# CI_iCESDuck-ShieldControler.net
KiCad netlist of a schematic drawn in EasyEDA
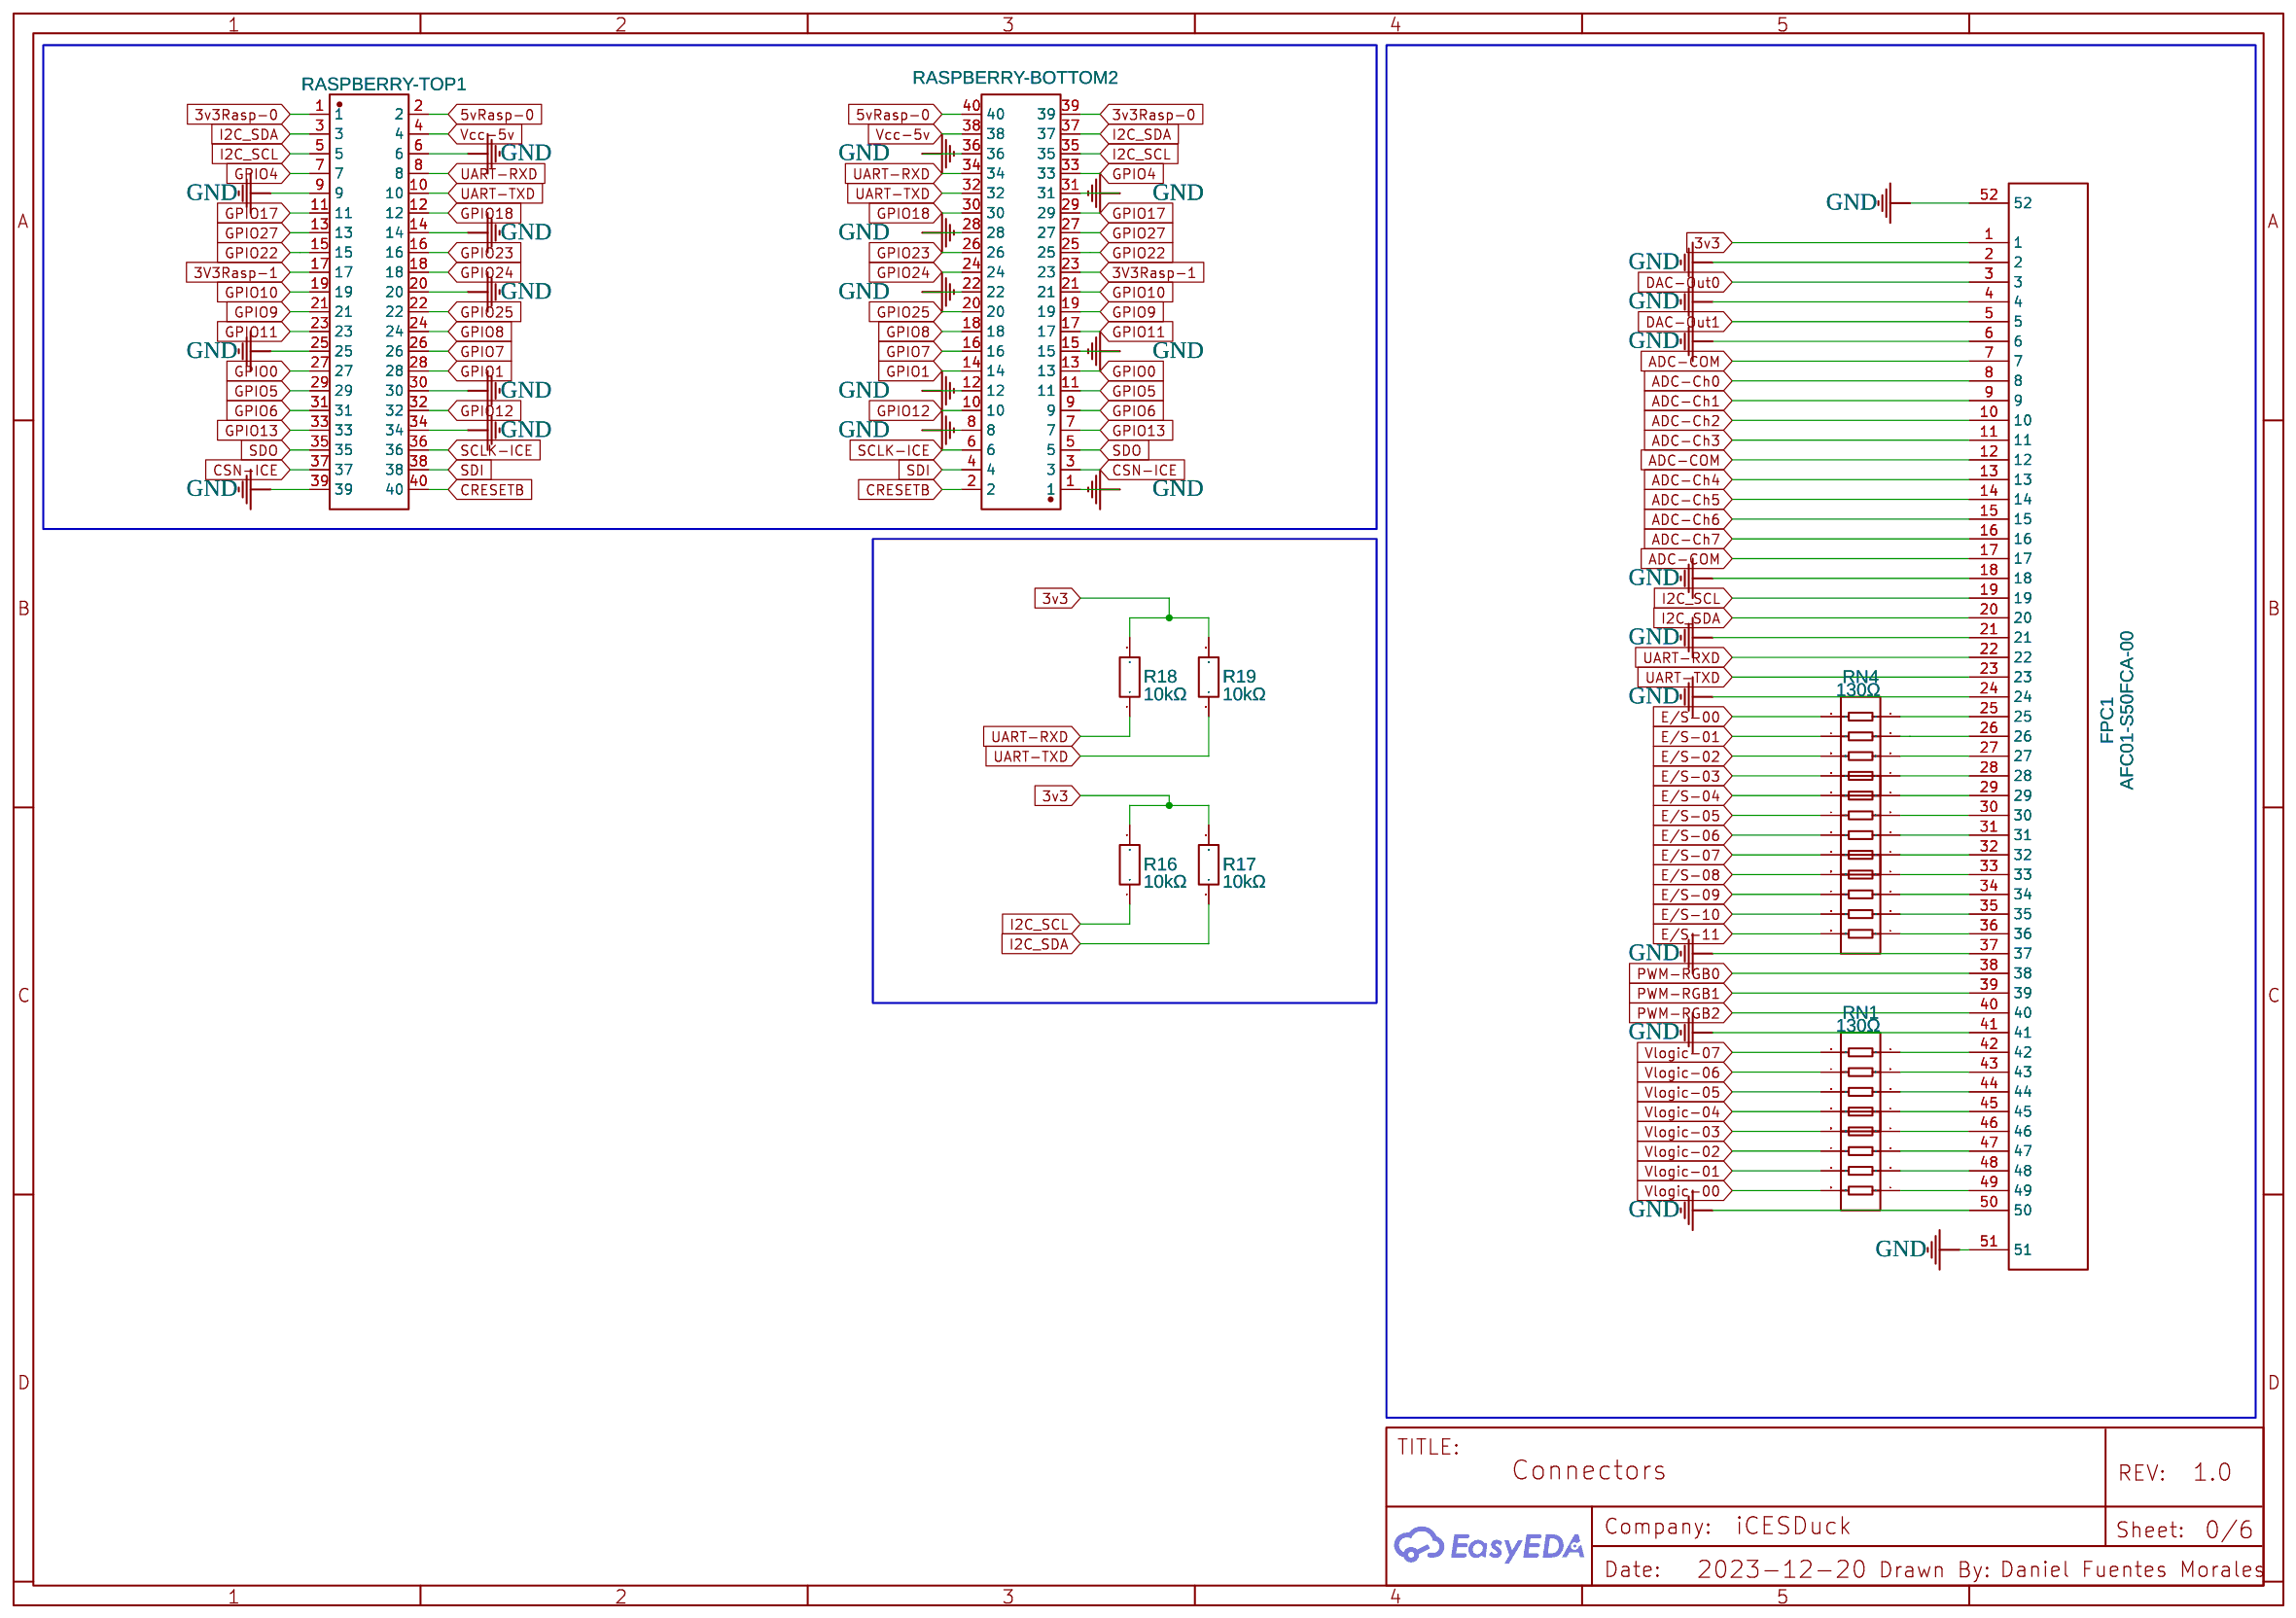
[diagram p0: Connectors]
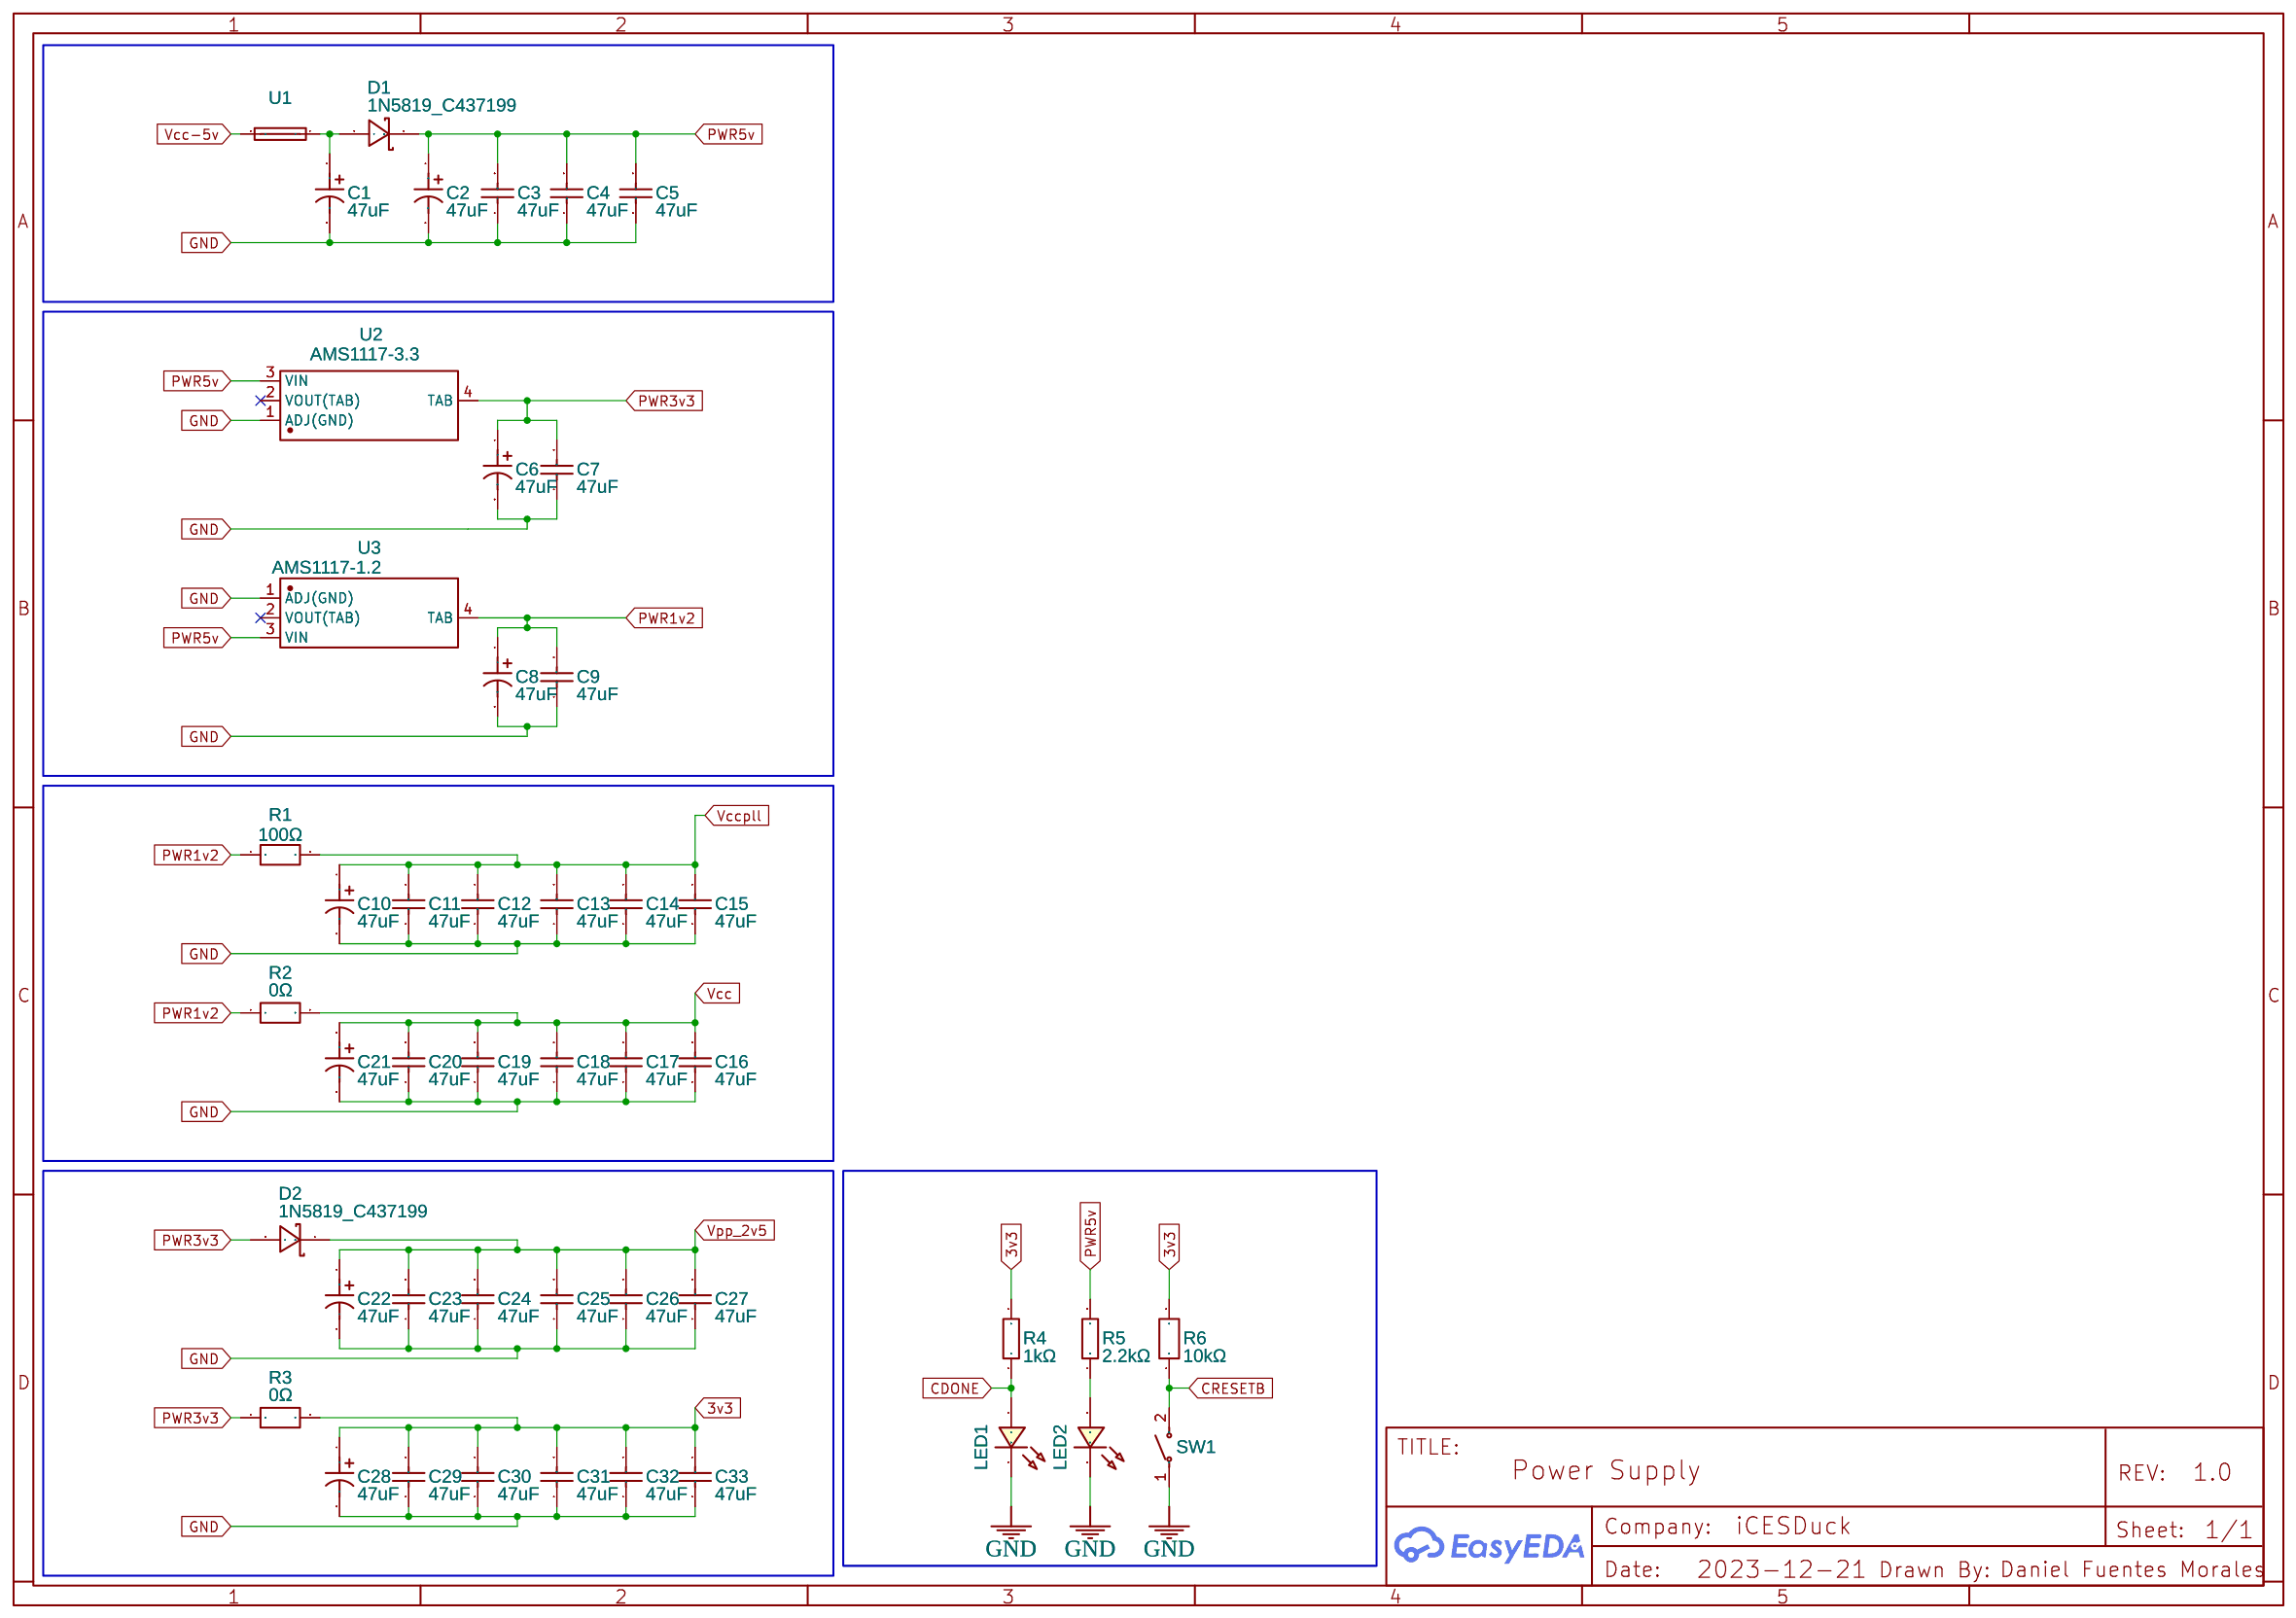
[diagram p1: power supply]
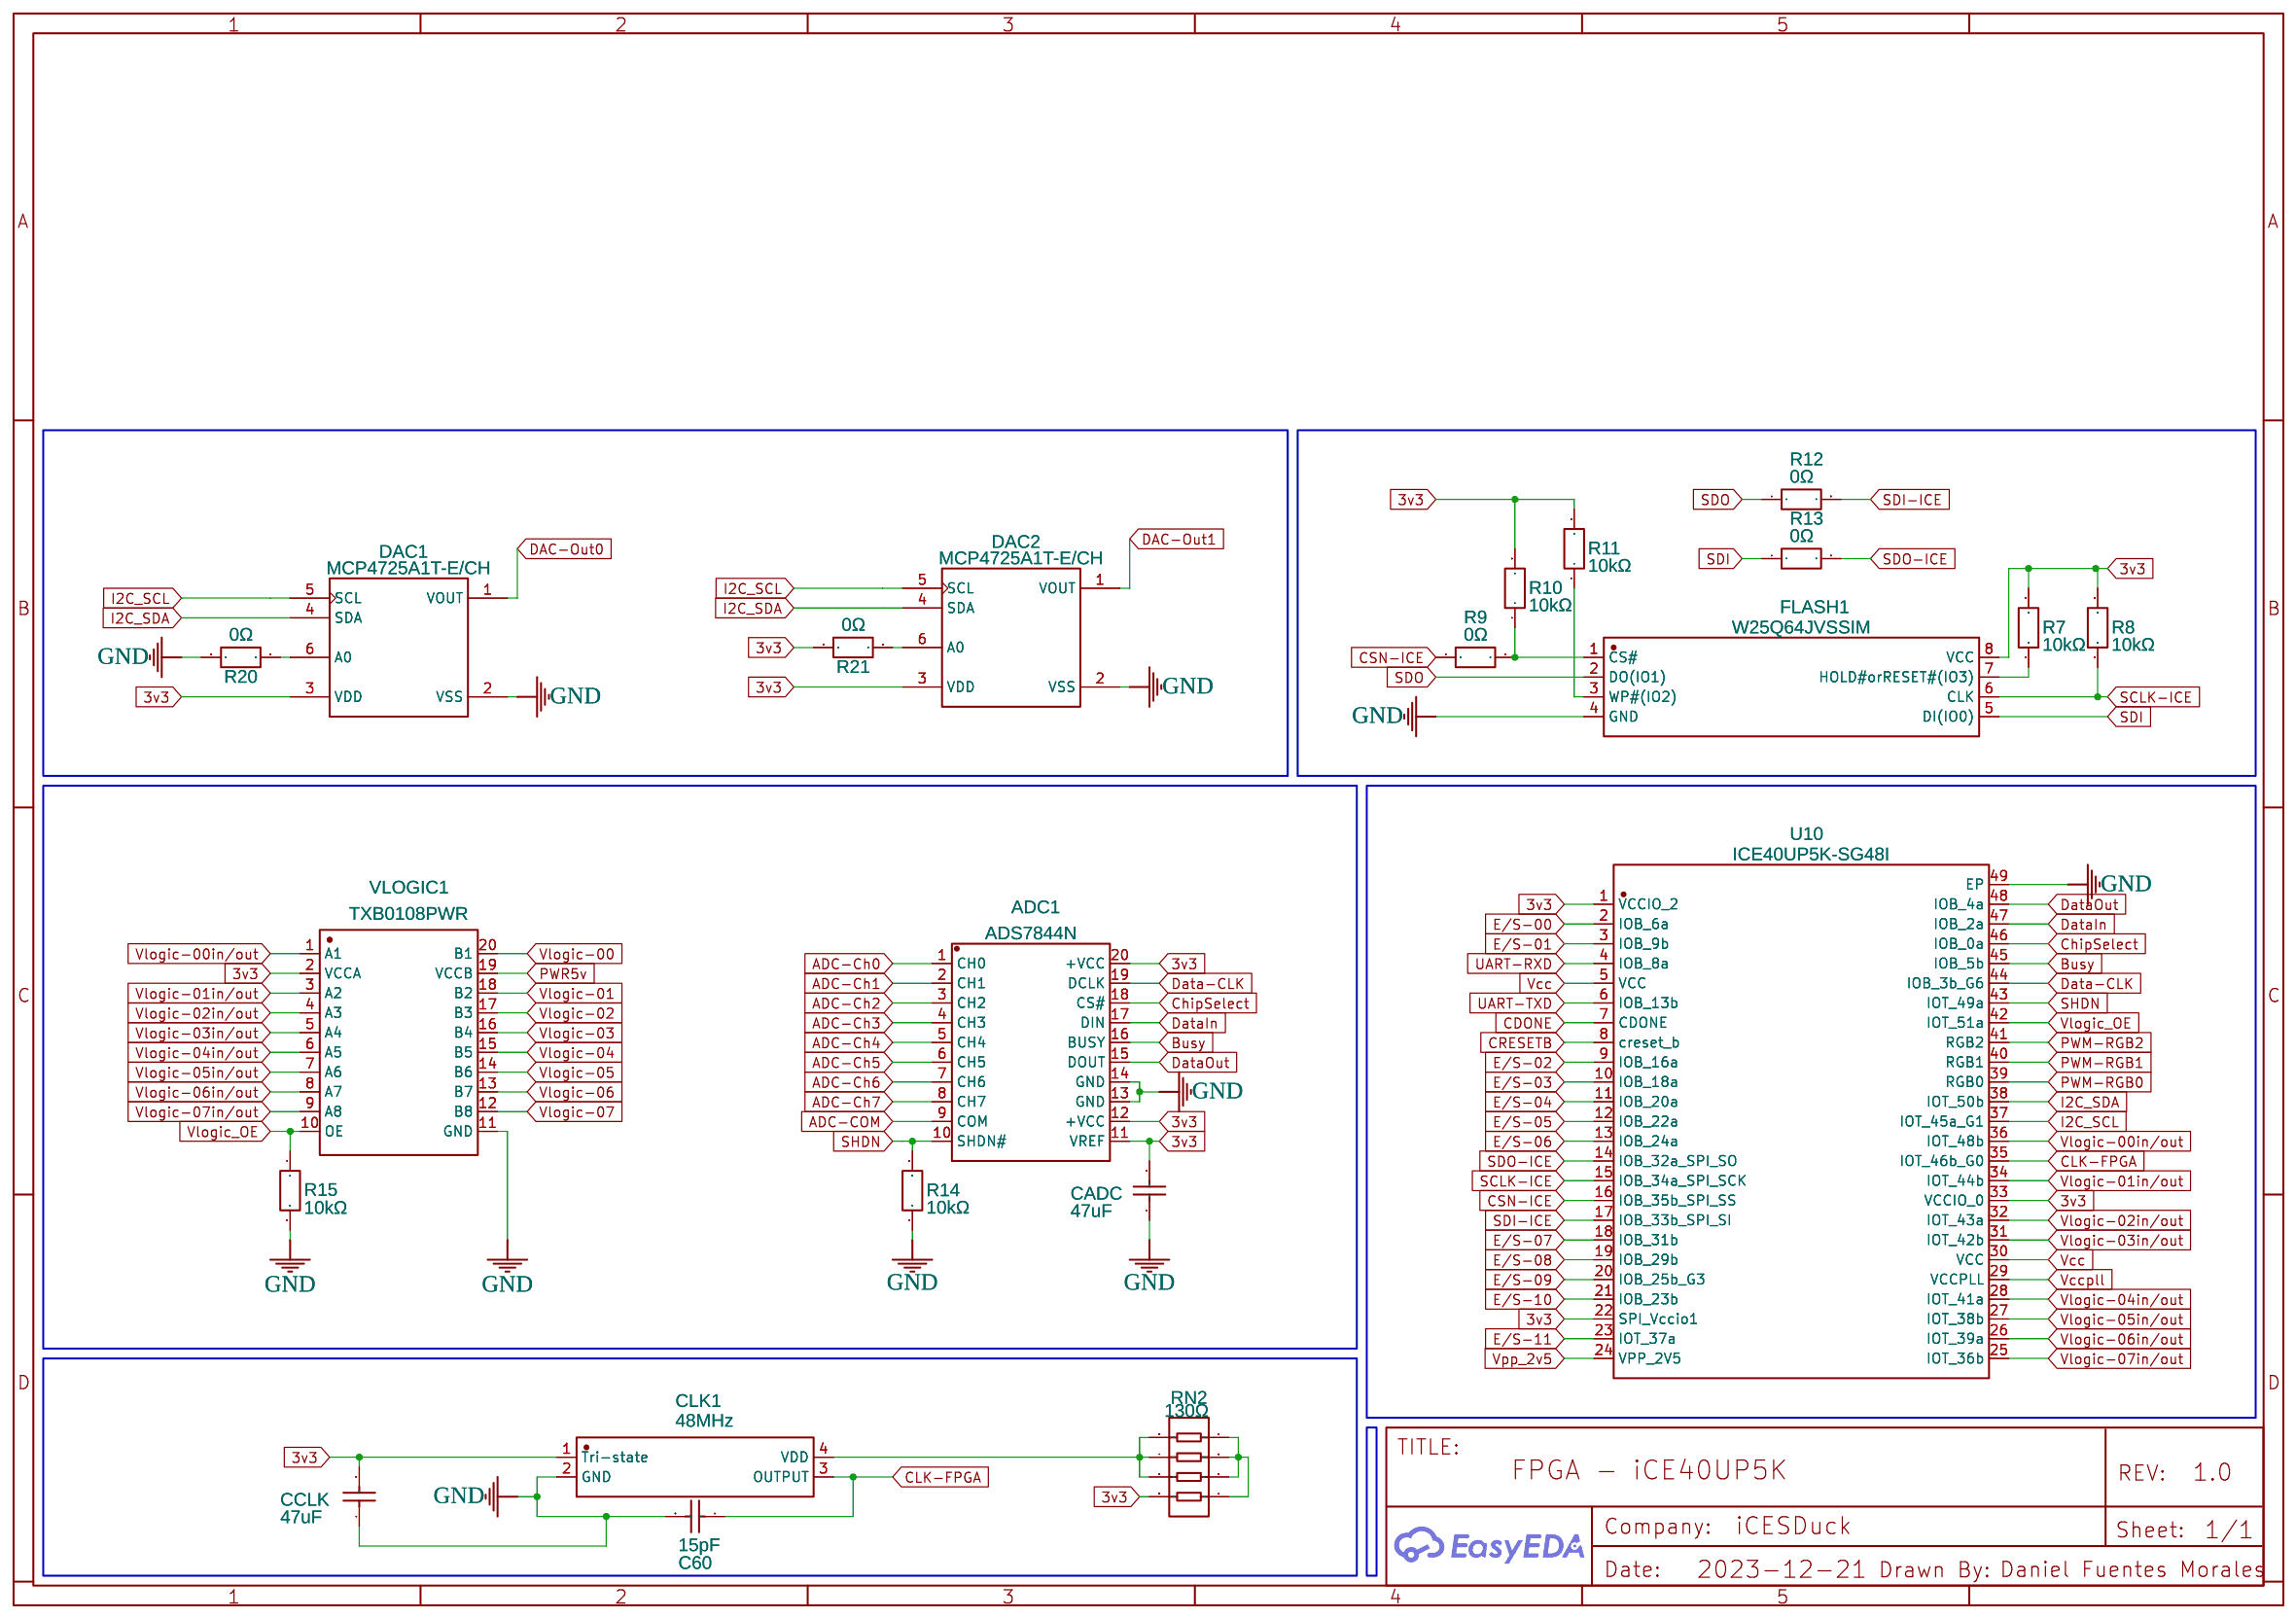
[diagram p2: FPGA - iCE40UP5k]

(export (version "E")
  (design (tool "Eeschema 10.0.6"))
  (components
    (comp (ref "FPC1")
      (value "AFC01-S50FCA-00")
      (fields (field (name "Manufacturer") "JS(钜硕电子)"))
      (libsource (lib "") (part "AFC01-S50FCA-00"))
    )
    (comp (ref "R16")
      (value "10kΩ")
      (fields (field (name "Manufacturer Part") "FRP1206J103 TS") (field (name "Manufacturer") "FOJAN(富捷)"))
      (libsource (lib "") (part "FRP1206J103 TS"))
    )
    (comp (ref "R17")
      (value "10kΩ")
      (fields (field (name "Manufacturer Part") "FRP1206J103 TS") (field (name "Manufacturer") "FOJAN(富捷)"))
      (libsource (lib "") (part "FRP1206J103 TS"))
    )
    (comp (ref "R18")
      (value "10kΩ")
      (fields (field (name "Manufacturer Part") "FRP1206J103 TS") (field (name "Manufacturer") "FOJAN(富捷)"))
      (libsource (lib "") (part "FRP1206J103 TS"))
    )
    (comp (ref "R19")
      (value "10kΩ")
      (fields (field (name "Manufacturer Part") "FRP1206J103 TS") (field (name "Manufacturer") "FOJAN(富捷)"))
      (libsource (lib "") (part "FRP1206J103 TS"))
    )
    (comp (ref "RASPBERRY-BOTTOM2")
      (value "FH-00148")
      (fields (field (name "Manufacturer") "Liansheng(连盛)"))
      (libsource (lib "") (part "FH-00148_1"))
    )
    (comp (ref "RASPBERRY-TOP1")
      (value "FH-00148")
      (fields (field (name "Manufacturer") "Liansheng(连盛)"))
      (libsource (lib "") (part "FH-00148"))
    )
    (comp (ref "RN1")
      (value "130Ω")
      (fields
        (field (name "Manufacturer Part") "4D03WGJ0131T5E")
        (field (name "Manufacturer") "UNI-ROYAL(厚声)")
      )
      (libsource (lib "") (part "4D03WGJ0131T5E"))
    )
    (comp (ref "RN3")
      (value "130Ω")
      (fields
        (field (name "Manufacturer Part") "4D03WGJ0131T5E")
        (field (name "Manufacturer") "UNI-ROYAL(厚声)")
      )
      (libsource (lib "") (part "4D03WGJ0131T5E"))
    )
    (comp (ref "RN4")
      (value "130Ω")
      (fields
        (field (name "Manufacturer Part") "4D03WGJ0131T5E")
        (field (name "Manufacturer") "UNI-ROYAL(厚声)")
      )
      (libsource (lib "") (part "4D03WGJ0131T5E"))
    )
    (comp (ref "RN5")
      (value "130Ω")
      (fields
        (field (name "Manufacturer Part") "4D03WGJ0131T5E")
        (field (name "Manufacturer") "UNI-ROYAL(厚声)")
      )
      (libsource (lib "") (part "4D03WGJ0131T5E"))
    )
    (comp (ref "RN6")
      (value "130Ω")
      (fields
        (field (name "Manufacturer Part") "4D03WGJ0131T5E")
        (field (name "Manufacturer") "UNI-ROYAL(厚声)")
      )
      (libsource (lib "") (part "4D03WGJ0131T5E"))
    )
    (comp (ref "C1")
      (value "47uF")
      (fields
        (field (name "Manufacturer Part") "CA45-A-10V-47uF-M")
        (field (name "Manufacturer") "CEC(振华新云)")
      )
      (libsource (lib "") (part "CA45-A-10V-47UF-M"))
    )
    (comp (ref "C2")
      (value "47uF")
      (fields
        (field (name "Manufacturer Part") "CA45-A-10V-47uF-M")
        (field (name "Manufacturer") "CEC(振华新云)")
      )
      (libsource (lib "") (part "CA45-A-10V-47UF-M"))
    )
    (comp (ref "C3")
      (value "47uF")
      (fields (field (name "Manufacturer Part") "C2012X5R1A476MTJ00E") (field (name "Manufacturer") "TDK"))
      (libsource (lib "") (part "C2012X5R1A476MTJ00E"))
    )
    (comp (ref "C4")
      (value "47uF")
      (fields (field (name "Manufacturer Part") "C2012X5R1A476MTJ00E") (field (name "Manufacturer") "TDK"))
      (libsource (lib "") (part "C2012X5R1A476MTJ00E"))
    )
    (comp (ref "C5")
      (value "47uF")
      (fields (field (name "Manufacturer Part") "C2012X5R1A476MTJ00E") (field (name "Manufacturer") "TDK"))
      (libsource (lib "") (part "C2012X5R1A476MTJ00E"))
    )
    (comp (ref "C6")
      (value "47uF")
      (fields
        (field (name "Manufacturer Part") "CA45-A-10V-47uF-M")
        (field (name "Manufacturer") "CEC(振华新云)")
      )
      (libsource (lib "") (part "CA45-A-10V-47UF-M"))
    )
    (comp (ref "C7")
      (value "47uF")
      (fields (field (name "Manufacturer Part") "C2012X5R1A476MTJ00E") (field (name "Manufacturer") "TDK"))
      (libsource (lib "") (part "C2012X5R1A476MTJ00E"))
    )
    (comp (ref "C8")
      (value "47uF")
      (fields
        (field (name "Manufacturer Part") "CA45-A-10V-47uF-M")
        (field (name "Manufacturer") "CEC(振华新云)")
      )
      (libsource (lib "") (part "CA45-A-10V-47UF-M"))
    )
    (comp (ref "C9")
      (value "47uF")
      (fields (field (name "Manufacturer Part") "C2012X5R1A476MTJ00E") (field (name "Manufacturer") "TDK"))
      (libsource (lib "") (part "C2012X5R1A476MTJ00E"))
    )
    (comp (ref "C10")
      (value "47uF")
      (fields
        (field (name "Manufacturer Part") "CA45-A-10V-47uF-M")
        (field (name "Manufacturer") "CEC(振华新云)")
      )
      (libsource (lib "") (part "CA45-A-10V-47UF-M"))
    )
    (comp (ref "C11")
      (value "47uF")
      (fields (field (name "Manufacturer Part") "C2012X5R1A476MTJ00E") (field (name "Manufacturer") "TDK"))
      (libsource (lib "") (part "C2012X5R1A476MTJ00E"))
    )
    (comp (ref "C12")
      (value "47uF")
      (fields (field (name "Manufacturer Part") "C2012X5R1A476MTJ00E") (field (name "Manufacturer") "TDK"))
      (libsource (lib "") (part "C2012X5R1A476MTJ00E"))
    )
    (comp (ref "C13")
      (value "47uF")
      (fields (field (name "Manufacturer Part") "C2012X5R1A476MTJ00E") (field (name "Manufacturer") "TDK"))
      (libsource (lib "") (part "C2012X5R1A476MTJ00E"))
    )
    (comp (ref "C14")
      (value "47uF")
      (fields (field (name "Manufacturer Part") "C2012X5R1A476MTJ00E") (field (name "Manufacturer") "TDK"))
      (libsource (lib "") (part "C2012X5R1A476MTJ00E"))
    )
    (comp (ref "C15")
      (value "47uF")
      (fields (field (name "Manufacturer Part") "C2012X5R1A476MTJ00E") (field (name "Manufacturer") "TDK"))
      (libsource (lib "") (part "C2012X5R1A476MTJ00E"))
    )
    (comp (ref "C16")
      (value "47uF")
      (fields (field (name "Manufacturer Part") "C2012X5R1A476MTJ00E") (field (name "Manufacturer") "TDK"))
      (libsource (lib "") (part "C2012X5R1A476MTJ00E"))
    )
    (comp (ref "C17")
      (value "47uF")
      (fields (field (name "Manufacturer Part") "C2012X5R1A476MTJ00E") (field (name "Manufacturer") "TDK"))
      (libsource (lib "") (part "C2012X5R1A476MTJ00E"))
    )
    (comp (ref "C18")
      (value "47uF")
      (fields (field (name "Manufacturer Part") "C2012X5R1A476MTJ00E") (field (name "Manufacturer") "TDK"))
      (libsource (lib "") (part "C2012X5R1A476MTJ00E"))
    )
    (comp (ref "C19")
      (value "47uF")
      (fields (field (name "Manufacturer Part") "C2012X5R1A476MTJ00E") (field (name "Manufacturer") "TDK"))
      (libsource (lib "") (part "C2012X5R1A476MTJ00E"))
    )
    (comp (ref "C20")
      (value "47uF")
      (fields (field (name "Manufacturer Part") "C2012X5R1A476MTJ00E") (field (name "Manufacturer") "TDK"))
      (libsource (lib "") (part "C2012X5R1A476MTJ00E"))
    )
    (comp (ref "C21")
      (value "47uF")
      (fields
        (field (name "Manufacturer Part") "CA45-A-10V-47uF-M")
        (field (name "Manufacturer") "CEC(振华新云)")
      )
      (libsource (lib "") (part "CA45-A-10V-47UF-M"))
    )
    (comp (ref "C22")
      (value "47uF")
      (fields
        (field (name "Manufacturer Part") "CA45-A-10V-47uF-M")
        (field (name "Manufacturer") "CEC(振华新云)")
      )
      (libsource (lib "") (part "CA45-A-10V-47UF-M"))
    )
    (comp (ref "C23")
      (value "47uF")
      (fields (field (name "Manufacturer Part") "C2012X5R1A476MTJ00E") (field (name "Manufacturer") "TDK"))
      (libsource (lib "") (part "C2012X5R1A476MTJ00E"))
    )
    (comp (ref "C24")
      (value "47uF")
      (fields (field (name "Manufacturer Part") "C2012X5R1A476MTJ00E") (field (name "Manufacturer") "TDK"))
      (libsource (lib "") (part "C2012X5R1A476MTJ00E"))
    )
    (comp (ref "C25")
      (value "47uF")
      (fields (field (name "Manufacturer Part") "C2012X5R1A476MTJ00E") (field (name "Manufacturer") "TDK"))
      (libsource (lib "") (part "C2012X5R1A476MTJ00E"))
    )
    (comp (ref "C26")
      (value "47uF")
      (fields (field (name "Manufacturer Part") "C2012X5R1A476MTJ00E") (field (name "Manufacturer") "TDK"))
      (libsource (lib "") (part "C2012X5R1A476MTJ00E"))
    )
    (comp (ref "C27")
      (value "47uF")
      (fields (field (name "Manufacturer Part") "C2012X5R1A476MTJ00E") (field (name "Manufacturer") "TDK"))
      (libsource (lib "") (part "C2012X5R1A476MTJ00E"))
    )
    (comp (ref "C28")
      (value "47uF")
      (fields
        (field (name "Manufacturer Part") "CA45-A-10V-47uF-M")
        (field (name "Manufacturer") "CEC(振华新云)")
      )
      (libsource (lib "") (part "CA45-A-10V-47UF-M"))
    )
    (comp (ref "C29")
      (value "47uF")
      (fields (field (name "Manufacturer Part") "C2012X5R1A476MTJ00E") (field (name "Manufacturer") "TDK"))
      (libsource (lib "") (part "C2012X5R1A476MTJ00E"))
    )
    (comp (ref "C30")
      (value "47uF")
      (fields (field (name "Manufacturer Part") "C2012X5R1A476MTJ00E") (field (name "Manufacturer") "TDK"))
      (libsource (lib "") (part "C2012X5R1A476MTJ00E"))
    )
    (comp (ref "C31")
      (value "47uF")
      (fields (field (name "Manufacturer Part") "C2012X5R1A476MTJ00E") (field (name "Manufacturer") "TDK"))
      (libsource (lib "") (part "C2012X5R1A476MTJ00E"))
    )
    (comp (ref "C32")
      (value "47uF")
      (fields (field (name "Manufacturer Part") "C2012X5R1A476MTJ00E") (field (name "Manufacturer") "TDK"))
      (libsource (lib "") (part "C2012X5R1A476MTJ00E"))
    )
    (comp (ref "C33")
      (value "47uF")
      (fields (field (name "Manufacturer Part") "C2012X5R1A476MTJ00E") (field (name "Manufacturer") "TDK"))
      (libsource (lib "") (part "C2012X5R1A476MTJ00E"))
    )
    (comp (ref "D1")
      (value "1N5819_C437199")
      (fields (field (name "Manufacturer Part") "1N5819") (field (name "Manufacturer") "KEXIN(科信)"))
      (libsource (lib "") (part "1N5819_C437199"))
    )
    (comp (ref "D2")
      (value "1N5819_C437199")
      (fields (field (name "Manufacturer Part") "1N5819") (field (name "Manufacturer") "KEXIN(科信)"))
      (libsource (lib "") (part "1N5819_C437199"))
    )
    (comp (ref "LED1")
      (value "LED-0603_G")
      (fields
        (field (name "Manufacturer Part") "19-217/GHC-YR1S2/3T")
        (field (name "Manufacturer") "EVERLIGHT(台湾亿光)")
      )
      (libsource (lib "") (part "LED-0603_G"))
    )
    (comp (ref "LED2")
      (value "LED-0603_G")
      (fields
        (field (name "Manufacturer Part") "19-217/GHC-YR1S2/3T")
        (field (name "Manufacturer") "EVERLIGHT(台湾亿光)")
      )
      (libsource (lib "") (part "LED-0603_G"))
    )
    (comp (ref "R1")
      (value "100Ω")
      (fields
        (field (name "Manufacturer Part") "AS05W2J0102T5E")
        (field (name "Manufacturer") "UNI-ROYAL(厚声)")
      )
      (libsource (lib "") (part "AS05W2J0102T5E"))
    )
    (comp (ref "R2")
      (value "0Ω")
      (fields
        (field (name "Manufacturer Part") "AS05W2J0102T5E")
        (field (name "Manufacturer") "UNI-ROYAL(厚声)")
      )
      (libsource (lib "") (part "AS05W2J0102T5E"))
    )
    (comp (ref "R3")
      (value "0Ω")
      (fields
        (field (name "Manufacturer Part") "AS05W2J0102T5E")
        (field (name "Manufacturer") "UNI-ROYAL(厚声)")
      )
      (libsource (lib "") (part "AS05W2J0102T5E"))
    )
    (comp (ref "R4")
      (value "1kΩ")
      (fields
        (field (name "Manufacturer Part") "0603WAF1001T5E")
        (field (name "Manufacturer") "UNI-ROYAL(厚声)")
      )
      (libsource (lib "") (part "0603WAF1001T5E"))
    )
    (comp (ref "R5")
      (value "2.2kΩ")
      (fields
        (field (name "Manufacturer Part") "0603WAF2201T5E")
        (field (name "Manufacturer") "UNI-ROYAL(厚声)")
      )
      (libsource (lib "") (part "0603WAF2201T5E"))
    )
    (comp (ref "R6")
      (value "10kΩ")
      (fields (field (name "Manufacturer Part") "FRP1206J103 TS") (field (name "Manufacturer") "FOJAN(富捷)"))
      (libsource (lib "") (part "FRP1206J103 TS"))
    )
    (comp (ref "SW1")
      (value "TS-1088R-02026")
      (fields (field (name "Manufacturer") "XUNPU(讯普)"))
      (libsource (lib "") (part "TS-1088R-02026"))
    )
    (comp (ref "U1")
      (value "0494001.NR")
      (fields (field (name "Manufacturer") "Littelfuse(美国力特)"))
      (libsource (lib "") (part "0494001.NR"))
    )
    (comp (ref "U2")
      (value "AMS1117-3.3")
      (fields (field (name "Manufacturer") "UMW(广东友台半导体)"))
      (libsource (lib "") (part "AMS1117-3.3_C347222"))
    )
    (comp (ref "U3")
      (value "AMS1117-1.2")
      (fields (field (name "Manufacturer") "UMW(广东友台半导体)"))
      (libsource (lib "") (part "AMS1117-1.2_C347218"))
    )
    (comp (ref "ADC1")
      (value "ADS7844N")
      (fields (field (name "Manufacturer") "TI(德州仪器)"))
      (libsource (lib "") (part "ADS7844N"))
    )
    (comp (ref "C60")
      (value "15pF")
      (fields
        (field (name "Manufacturer Part") "CL10C150JB8NNNC")
        (field (name "Manufacturer") "SAMSUNG(三星)")
      )
      (libsource (lib "") (part "CL10C150JB8NNNC"))
    )
    (comp (ref "CADC")
      (value "47uF")
      (fields (field (name "Manufacturer Part") "C2012X5R1A476MTJ00E") (field (name "Manufacturer") "TDK"))
      (libsource (lib "") (part "C2012X5R1A476MTJ00E"))
    )
    (comp (ref "CCLK")
      (value "47uF")
      (fields (field (name "Manufacturer Part") "C2012X5R1A476MTJ00E") (field (name "Manufacturer") "TDK"))
      (libsource (lib "") (part "C2012X5R1A476MTJ00E_1"))
    )
    (comp (ref "CLK1")
      (value "48MHz")
      (fields
        (field (name "Manufacturer Part") "S3D48.000000B20F30T")
        (field (name "Manufacturer") "SCTF(星通时频)")
      )
      (libsource (lib "") (part "S3D48.000000B20F30T"))
    )
    (comp (ref "DAC1")
      (value "MCP4725A1T-E/CH")
      (fields (field (name "Manufacturer") "MICROCHIP(美国微芯)"))
      (libsource (lib "") (part "MCP4725A1T-E/CH"))
    )
    (comp (ref "DAC2")
      (value "MCP4725A1T-E/CH")
      (fields (field (name "Manufacturer") "MICROCHIP(美国微芯)"))
      (libsource (lib "") (part "MCP4725A1T-E/CH"))
    )
    (comp (ref "FLASH1")
      (value "W25Q64JVSSIM")
      (fields (field (name "Manufacturer") "WINBOND(华邦)"))
      (libsource (lib "") (part "W25Q64JVSSIM"))
    )
    (comp (ref "R7")
      (value "10kΩ")
      (fields (field (name "Manufacturer Part") "FRP1206J103 TS") (field (name "Manufacturer") "FOJAN(富捷)"))
      (libsource (lib "") (part "FRP1206J103 TS"))
    )
    (comp (ref "R8")
      (value "10kΩ")
      (fields (field (name "Manufacturer Part") "FRP1206J103 TS") (field (name "Manufacturer") "FOJAN(富捷)"))
      (libsource (lib "") (part "FRP1206J103 TS"))
    )
    (comp (ref "R9")
      (value "0Ω")
      (fields
        (field (name "Manufacturer Part") "AS05W2J0102T5E")
        (field (name "Manufacturer") "UNI-ROYAL(厚声)")
      )
      (libsource (lib "") (part "AS05W2J0102T5E"))
    )
    (comp (ref "R10")
      (value "10kΩ")
      (fields (field (name "Manufacturer Part") "FRP1206J103 TS") (field (name "Manufacturer") "FOJAN(富捷)"))
      (libsource (lib "") (part "FRP1206J103 TS"))
    )
    (comp (ref "R11")
      (value "10kΩ")
      (fields (field (name "Manufacturer Part") "FRP1206J103 TS") (field (name "Manufacturer") "FOJAN(富捷)"))
      (libsource (lib "") (part "FRP1206J103 TS"))
    )
    (comp (ref "R12")
      (value "0Ω")
      (fields
        (field (name "Manufacturer Part") "AS05W2J0102T5E")
        (field (name "Manufacturer") "UNI-ROYAL(厚声)")
      )
      (libsource (lib "") (part "AS05W2J0102T5E"))
    )
    (comp (ref "R13")
      (value "0Ω")
      (fields
        (field (name "Manufacturer Part") "AS05W2J0102T5E")
        (field (name "Manufacturer") "UNI-ROYAL(厚声)")
      )
      (libsource (lib "") (part "AS05W2J0102T5E"))
    )
    (comp (ref "R14")
      (value "10kΩ")
      (fields (field (name "Manufacturer Part") "FRP1206J103 TS") (field (name "Manufacturer") "FOJAN(富捷)"))
      (libsource (lib "") (part "FRP1206J103 TS"))
    )
    (comp (ref "R15")
      (value "10kΩ")
      (fields (field (name "Manufacturer Part") "FRP1206J103 TS") (field (name "Manufacturer") "FOJAN(富捷)"))
      (libsource (lib "") (part "FRP1206J103 TS_1"))
    )
    (comp (ref "R20")
      (value "0Ω")
      (fields
        (field (name "Manufacturer Part") "AS05W2J0102T5E")
        (field (name "Manufacturer") "UNI-ROYAL(厚声)")
      )
      (libsource (lib "") (part "AS05W2J0102T5E"))
    )
    (comp (ref "R21")
      (value "0Ω")
      (fields
        (field (name "Manufacturer Part") "AS05W2J0102T5E")
        (field (name "Manufacturer") "UNI-ROYAL(厚声)")
      )
      (libsource (lib "") (part "AS05W2J0102T5E"))
    )
    (comp (ref "RN2")
      (value "130Ω")
      (fields
        (field (name "Manufacturer Part") "4D03WGJ0131T5E")
        (field (name "Manufacturer") "UNI-ROYAL(厚声)")
      )
      (libsource (lib "") (part "4D03WGJ0131T5E"))
    )
    (comp (ref "U10")
      (value "ICE40UP5K-SG48I")
      (fields (field (name "Manufacturer") "LATTICE(莱迪思)"))
      (libsource (lib "") (part "ICE40UP5K-SG48I"))
    )
    (comp (ref "VLOGIC1")
      (value "TXB0108PWR")
      (fields (field (name "Manufacturer") "TI(德州仪器)"))
      (libsource (lib "") (part "TXB0108PWR"))
    )
  )
  (nets
    (net (code "1") (name "3V3Rasp-1") (class "Default")
      (node (ref "RASPBERRY-BOTTOM2") (pin "23") (pinfunction "23_23") (pintype "unspecified"))
      (node (ref "RASPBERRY-TOP1") (pin "17") (pinfunction "17_17") (pintype "unspecified"))
    )
    (net (code "2") (name "3v3") (class "Default")
      (node (ref "ADC1") (pin "11") (pinfunction "VREF_11") (pintype "unspecified"))
      (node (ref "ADC1") (pin "12") (pinfunction "+VCC_12") (pintype "unspecified"))
      (node (ref "ADC1") (pin "20") (pinfunction "+VCC_20") (pintype "unspecified"))
      (node (ref "C28") (pin "1") (pinfunction "1_1") (pintype "input"))
      (node (ref "C29") (pin "2") (pinfunction "2_2") (pintype "input"))
      (node (ref "C30") (pin "2") (pinfunction "2_2") (pintype "input"))
      (node (ref "C31") (pin "2") (pinfunction "2_2") (pintype "input"))
      (node (ref "C32") (pin "2") (pinfunction "2_2") (pintype "input"))
      (node (ref "C33") (pin "2") (pinfunction "2_2") (pintype "input"))
      (node (ref "CADC") (pin "2") (pinfunction "2_2") (pintype "input"))
      (node (ref "CCLK") (pin "2") (pinfunction "2_2") (pintype "input"))
      (node (ref "CLK1") (pin "1") (pinfunction "Tri-state_1") (pintype "unspecified"))
      (node (ref "DAC1") (pin "3") (pinfunction "VDD_3") (pintype "passive"))
      (node (ref "DAC2") (pin "3") (pinfunction "VDD_3") (pintype "passive"))
      (node (ref "FLASH1") (pin "8") (pinfunction "VCC_8") (pintype "unspecified"))
      (node (ref "FPC1") (pin "1") (pinfunction "1_1") (pintype "unspecified"))
      (node (ref "R10") (pin "2") (pinfunction "2_2") (pintype "unspecified"))
      (node (ref "R11") (pin "2") (pinfunction "2_2") (pintype "unspecified"))
      (node (ref "R16") (pin "2") (pinfunction "2_2") (pintype "unspecified"))
      (node (ref "R17") (pin "2") (pinfunction "2_2") (pintype "unspecified"))
      (node (ref "R18") (pin "2") (pinfunction "2_2") (pintype "unspecified"))
      (node (ref "R19") (pin "2") (pinfunction "2_2") (pintype "unspecified"))
      (node (ref "R21") (pin "1") (pinfunction "1_1") (pintype "unspecified"))
      (node (ref "R3") (pin "2") (pinfunction "2_2") (pintype "unspecified"))
      (node (ref "R4") (pin "2") (pinfunction "2_2") (pintype "input"))
      (node (ref "R6") (pin "2") (pinfunction "2_2") (pintype "unspecified"))
      (node (ref "R7") (pin "2") (pinfunction "2_2") (pintype "unspecified"))
      (node (ref "R8") (pin "2") (pinfunction "2_2") (pintype "unspecified"))
      (node (ref "RN2") (pin "5") (pinfunction "5_5") (pintype "unspecified"))
      (node (ref "U10") (pin "1") (pinfunction "VCCIO_2_1") (pintype "unspecified"))
      (node (ref "U10") (pin "22") (pinfunction "SPI_Vccio1_22") (pintype "unspecified"))
      (node (ref "U10") (pin "33") (pinfunction "VCCIO_0_33") (pintype "unspecified"))
      (node (ref "VLOGIC1") (pin "2") (pinfunction "VCCA_2") (pintype "unspecified"))
    )
    (net (code "3") (name "3v3Rasp-0") (class "Default")
      (node (ref "RASPBERRY-BOTTOM2") (pin "39") (pinfunction "39_39") (pintype "unspecified"))
      (node (ref "RASPBERRY-TOP1") (pin "1") (pinfunction "1_1") (pintype "unspecified"))
    )
    (net (code "4") (name "5vRasp-0") (class "Default")
      (node (ref "RASPBERRY-BOTTOM2") (pin "40") (pinfunction "40_40") (pintype "unspecified"))
      (node (ref "RASPBERRY-TOP1") (pin "2") (pinfunction "2_2") (pintype "unspecified"))
    )
    (net (code "5") (name "ADC-COM") (class "Default")
      (node (ref "ADC1") (pin "9") (pinfunction "COM_9") (pintype "unspecified"))
      (node (ref "FPC1") (pin "12") (pinfunction "12_12") (pintype "unspecified"))
      (node (ref "FPC1") (pin "17") (pinfunction "17_17") (pintype "unspecified"))
      (node (ref "FPC1") (pin "7") (pinfunction "7_7") (pintype "unspecified"))
    )
    (net (code "6") (name "ADC-Ch0") (class "Default")
      (node (ref "ADC1") (pin "1") (pinfunction "CH0_1") (pintype "unspecified"))
      (node (ref "FPC1") (pin "8") (pinfunction "8_8") (pintype "unspecified"))
    )
    (net (code "7") (name "ADC-Ch1") (class "Default")
      (node (ref "ADC1") (pin "2") (pinfunction "CH1_2") (pintype "unspecified"))
      (node (ref "FPC1") (pin "9") (pinfunction "9_9") (pintype "unspecified"))
    )
    (net (code "8") (name "ADC-Ch2") (class "Default")
      (node (ref "ADC1") (pin "3") (pinfunction "CH2_3") (pintype "unspecified"))
      (node (ref "FPC1") (pin "10") (pinfunction "10_10") (pintype "unspecified"))
    )
    (net (code "9") (name "ADC-Ch3") (class "Default")
      (node (ref "ADC1") (pin "4") (pinfunction "CH3_4") (pintype "unspecified"))
      (node (ref "FPC1") (pin "11") (pinfunction "11_11") (pintype "unspecified"))
    )
    (net (code "10") (name "ADC-Ch4") (class "Default")
      (node (ref "ADC1") (pin "5") (pinfunction "CH4_5") (pintype "unspecified"))
      (node (ref "FPC1") (pin "13") (pinfunction "13_13") (pintype "unspecified"))
    )
    (net (code "11") (name "ADC-Ch5") (class "Default")
      (node (ref "ADC1") (pin "6") (pinfunction "CH5_6") (pintype "unspecified"))
      (node (ref "FPC1") (pin "14") (pinfunction "14_14") (pintype "unspecified"))
    )
    (net (code "12") (name "ADC-Ch6") (class "Default")
      (node (ref "ADC1") (pin "7") (pinfunction "CH6_7") (pintype "unspecified"))
      (node (ref "FPC1") (pin "15") (pinfunction "15_15") (pintype "unspecified"))
    )
    (net (code "13") (name "ADC-Ch7") (class "Default")
      (node (ref "ADC1") (pin "8") (pinfunction "CH7_8") (pintype "unspecified"))
      (node (ref "FPC1") (pin "16") (pinfunction "16_16") (pintype "unspecified"))
    )
    (net (code "14") (name "Busy") (class "Default")
      (node (ref "ADC1") (pin "16") (pinfunction "BUSY_16") (pintype "unspecified"))
      (node (ref "U10") (pin "45") (pinfunction "IOB_5b_45") (pintype "unspecified"))
    )
    (net (code "15") (name "CDONE") (class "Default")
      (node (ref "LED1") (pin "1") (pinfunction "1_1") (pintype "unspecified"))
      (node (ref "R4") (pin "1") (pinfunction "1_1") (pintype "input"))
      (node (ref "U10") (pin "7") (pinfunction "CDONE_7") (pintype "unspecified"))
    )
    (net (code "16") (name "CLK-FPGA") (class "Default")
      (node (ref "C60") (pin "1") (pinfunction "1_1") (pintype "input"))
      (node (ref "CLK1") (pin "3") (pinfunction "OUTPUT_3") (pintype "unspecified"))
      (node (ref "U10") (pin "35") (pinfunction "IOT_46b_G0_35") (pintype "unspecified"))
    )
    (net (code "17") (name "CRESETB") (class "Default")
      (node (ref "R6") (pin "1") (pinfunction "1_1") (pintype "unspecified"))
      (node (ref "RASPBERRY-BOTTOM2") (pin "2") (pinfunction "2_2") (pintype "unspecified"))
      (node (ref "RASPBERRY-TOP1") (pin "40") (pinfunction "40_40") (pintype "unspecified"))
      (node (ref "SW1") (pin "2") (pinfunction "2_2") (pintype "unspecified"))
      (node (ref "U10") (pin "8") (pinfunction "creset_b_8") (pintype "unspecified"))
    )
    (net (code "18") (name "CSN-ICE") (class "Default")
      (node (ref "R9") (pin "1") (pinfunction "1_1") (pintype "unspecified"))
      (node (ref "RASPBERRY-BOTTOM2") (pin "3") (pinfunction "3_3") (pintype "unspecified"))
      (node (ref "RASPBERRY-TOP1") (pin "37") (pinfunction "37_37") (pintype "unspecified"))
      (node (ref "U10") (pin "16") (pinfunction "IOB_35b_SPI_SS_16") (pintype "unspecified"))
    )
    (net (code "19") (name "ChipSelect") (class "Default")
      (node (ref "ADC1") (pin "18") (pinfunction "CS#_18") (pintype "unspecified"))
      (node (ref "U10") (pin "46") (pinfunction "IOB_0a_46") (pintype "unspecified"))
    )
    (net (code "20") (name "DAC-Out0") (class "Default")
      (node (ref "DAC1") (pin "1") (pinfunction "VOUT_1") (pintype "output"))
      (node (ref "FPC1") (pin "3") (pinfunction "3_3") (pintype "unspecified"))
    )
    (net (code "21") (name "DAC-Out1") (class "Default")
      (node (ref "DAC2") (pin "1") (pinfunction "VOUT_1") (pintype "output"))
      (node (ref "FPC1") (pin "5") (pinfunction "5_5") (pintype "unspecified"))
    )
    (net (code "22") (name "Data-CLK") (class "Default")
      (node (ref "ADC1") (pin "19") (pinfunction "DCLK_19") (pintype "unspecified"))
      (node (ref "U10") (pin "44") (pinfunction "IOB_3b_G6_44") (pintype "unspecified"))
    )
    (net (code "23") (name "DataIn") (class "Default")
      (node (ref "ADC1") (pin "17") (pinfunction "DIN_17") (pintype "unspecified"))
      (node (ref "U10") (pin "47") (pinfunction "IOB_2a_47") (pintype "unspecified"))
    )
    (net (code "24") (name "DataOut") (class "Default")
      (node (ref "ADC1") (pin "15") (pinfunction "DOUT_15") (pintype "unspecified"))
      (node (ref "U10") (pin "48") (pinfunction "IOB_4a_48") (pintype "unspecified"))
    )
    (net (code "25") (name "E{slash}S-00") (class "Default")
      (node (ref "RN4") (pin "8") (pinfunction "8_8") (pintype "unspecified"))
      (node (ref "U10") (pin "2") (pinfunction "IOB_6a_2") (pintype "unspecified"))
    )
    (net (code "26") (name "E{slash}S-01") (class "Default")
      (node (ref "RN4") (pin "7") (pinfunction "7_7") (pintype "unspecified"))
      (node (ref "U10") (pin "3") (pinfunction "IOB_9b_3") (pintype "unspecified"))
    )
    (net (code "27") (name "E{slash}S-02") (class "Default")
      (node (ref "RN4") (pin "6") (pinfunction "6_6") (pintype "unspecified"))
      (node (ref "U10") (pin "9") (pinfunction "IOB_16a_9") (pintype "unspecified"))
    )
    (net (code "28") (name "E{slash}S-03") (class "Default")
      (node (ref "RN4") (pin "5") (pinfunction "5_5") (pintype "unspecified"))
      (node (ref "U10") (pin "10") (pinfunction "IOB_18a_10") (pintype "unspecified"))
    )
    (net (code "29") (name "E{slash}S-04") (class "Default")
      (node (ref "RN5") (pin "8") (pinfunction "8_8") (pintype "unspecified"))
      (node (ref "U10") (pin "11") (pinfunction "IOB_20a_11") (pintype "unspecified"))
    )
    (net (code "30") (name "E{slash}S-05") (class "Default")
      (node (ref "RN5") (pin "7") (pinfunction "7_7") (pintype "unspecified"))
      (node (ref "U10") (pin "12") (pinfunction "IOB_22a_12") (pintype "unspecified"))
    )
    (net (code "31") (name "E{slash}S-06") (class "Default")
      (node (ref "RN5") (pin "6") (pinfunction "6_6") (pintype "unspecified"))
      (node (ref "U10") (pin "13") (pinfunction "IOB_24a_13") (pintype "unspecified"))
    )
    (net (code "32") (name "E{slash}S-07") (class "Default")
      (node (ref "RN5") (pin "5") (pinfunction "5_5") (pintype "unspecified"))
      (node (ref "U10") (pin "18") (pinfunction "IOB_31b_18") (pintype "unspecified"))
    )
    (net (code "33") (name "E{slash}S-08") (class "Default")
      (node (ref "RN6") (pin "8") (pinfunction "8_8") (pintype "unspecified"))
      (node (ref "U10") (pin "19") (pinfunction "IOB_29b_19") (pintype "unspecified"))
    )
    (net (code "34") (name "E{slash}S-09") (class "Default")
      (node (ref "RN6") (pin "7") (pinfunction "7_7") (pintype "unspecified"))
      (node (ref "U10") (pin "20") (pinfunction "IOB_25b_G3_20") (pintype "unspecified"))
    )
    (net (code "35") (name "E{slash}S-10") (class "Default")
      (node (ref "RN6") (pin "6") (pinfunction "6_6") (pintype "unspecified"))
      (node (ref "U10") (pin "21") (pinfunction "IOB_23b_21") (pintype "unspecified"))
    )
    (net (code "36") (name "E{slash}S-11") (class "Default")
      (node (ref "RN6") (pin "5") (pinfunction "5_5") (pintype "unspecified"))
      (node (ref "U10") (pin "23") (pinfunction "IOT_37a_23") (pintype "unspecified"))
    )
    (net (code "37") (name "GND") (class "Default")
      (node (ref "ADC1") (pin "13") (pinfunction "GND_13") (pintype "unspecified"))
      (node (ref "ADC1") (pin "14") (pinfunction "GND_14") (pintype "unspecified"))
      (node (ref "C1") (pin "2") (pinfunction "2_2") (pintype "input"))
      (node (ref "C10") (pin "2") (pinfunction "2_2") (pintype "input"))
      (node (ref "C11") (pin "1") (pinfunction "1_1") (pintype "input"))
      (node (ref "C12") (pin "1") (pinfunction "1_1") (pintype "input"))
      (node (ref "C13") (pin "1") (pinfunction "1_1") (pintype "input"))
      (node (ref "C14") (pin "1") (pinfunction "1_1") (pintype "input"))
      (node (ref "C15") (pin "1") (pinfunction "1_1") (pintype "input"))
      (node (ref "C16") (pin "1") (pinfunction "1_1") (pintype "input"))
      (node (ref "C17") (pin "1") (pinfunction "1_1") (pintype "input"))
      (node (ref "C18") (pin "1") (pinfunction "1_1") (pintype "input"))
      (node (ref "C19") (pin "1") (pinfunction "1_1") (pintype "input"))
      (node (ref "C2") (pin "2") (pinfunction "2_2") (pintype "input"))
      (node (ref "C20") (pin "1") (pinfunction "1_1") (pintype "input"))
      (node (ref "C21") (pin "2") (pinfunction "2_2") (pintype "input"))
      (node (ref "C22") (pin "2") (pinfunction "2_2") (pintype "input"))
      (node (ref "C23") (pin "1") (pinfunction "1_1") (pintype "input"))
      (node (ref "C24") (pin "1") (pinfunction "1_1") (pintype "input"))
      (node (ref "C25") (pin "1") (pinfunction "1_1") (pintype "input"))
      (node (ref "C26") (pin "1") (pinfunction "1_1") (pintype "input"))
      (node (ref "C27") (pin "1") (pinfunction "1_1") (pintype "input"))
      (node (ref "C28") (pin "2") (pinfunction "2_2") (pintype "input"))
      (node (ref "C29") (pin "1") (pinfunction "1_1") (pintype "input"))
      (node (ref "C3") (pin "1") (pinfunction "1_1") (pintype "input"))
      (node (ref "C30") (pin "1") (pinfunction "1_1") (pintype "input"))
      (node (ref "C31") (pin "1") (pinfunction "1_1") (pintype "input"))
      (node (ref "C32") (pin "1") (pinfunction "1_1") (pintype "input"))
      (node (ref "C33") (pin "1") (pinfunction "1_1") (pintype "input"))
      (node (ref "C4") (pin "1") (pinfunction "1_1") (pintype "input"))
      (node (ref "C5") (pin "1") (pinfunction "1_1") (pintype "input"))
      (node (ref "C6") (pin "2") (pinfunction "2_2") (pintype "input"))
      (node (ref "C60") (pin "2") (pinfunction "2_2") (pintype "input"))
      (node (ref "C7") (pin "1") (pinfunction "1_1") (pintype "input"))
      (node (ref "C8") (pin "2") (pinfunction "2_2") (pintype "input"))
      (node (ref "C9") (pin "1") (pinfunction "1_1") (pintype "input"))
      (node (ref "CADC") (pin "1") (pinfunction "1_1") (pintype "input"))
      (node (ref "CCLK") (pin "1") (pinfunction "1_1") (pintype "input"))
      (node (ref "CLK1") (pin "2") (pinfunction "GND_2") (pintype "unspecified"))
      (node (ref "DAC1") (pin "2") (pinfunction "VSS_2") (pintype "passive"))
      (node (ref "DAC2") (pin "2") (pinfunction "VSS_2") (pintype "passive"))
      (node (ref "FLASH1") (pin "4") (pinfunction "GND_4") (pintype "unspecified"))
      (node (ref "FPC1") (pin "18") (pinfunction "18_18") (pintype "unspecified"))
      (node (ref "FPC1") (pin "2") (pinfunction "2_2") (pintype "unspecified"))
      (node (ref "FPC1") (pin "21") (pinfunction "21_21") (pintype "unspecified"))
      (node (ref "FPC1") (pin "24") (pinfunction "24_24") (pintype "unspecified"))
      (node (ref "FPC1") (pin "37") (pinfunction "37_37") (pintype "unspecified"))
      (node (ref "FPC1") (pin "4") (pinfunction "4_4") (pintype "unspecified"))
      (node (ref "FPC1") (pin "41") (pinfunction "41_41") (pintype "unspecified"))
      (node (ref "FPC1") (pin "50") (pinfunction "50_50") (pintype "unspecified"))
      (node (ref "FPC1") (pin "51") (pinfunction "51_51") (pintype "unspecified"))
      (node (ref "FPC1") (pin "52") (pinfunction "52_52") (pintype "unspecified"))
      (node (ref "FPC1") (pin "6") (pinfunction "6_6") (pintype "unspecified"))
      (node (ref "LED1") (pin "2") (pinfunction "2_2") (pintype "unspecified"))
      (node (ref "LED2") (pin "2") (pinfunction "2_2") (pintype "unspecified"))
      (node (ref "R14") (pin "1") (pinfunction "1_1") (pintype "unspecified"))
      (node (ref "R15") (pin "2") (pinfunction "2_2") (pintype "unspecified"))
      (node (ref "R20") (pin "1") (pinfunction "1_1") (pintype "unspecified"))
      (node (ref "RASPBERRY-BOTTOM2") (pin "1") (pinfunction "1_1") (pintype "unspecified"))
      (node (ref "RASPBERRY-BOTTOM2") (pin "12") (pinfunction "12_12") (pintype "unspecified"))
      (node (ref "RASPBERRY-BOTTOM2") (pin "15") (pinfunction "15_15") (pintype "unspecified"))
      (node (ref "RASPBERRY-BOTTOM2") (pin "22") (pinfunction "22_22") (pintype "unspecified"))
      (node (ref "RASPBERRY-BOTTOM2") (pin "28") (pinfunction "28_28") (pintype "unspecified"))
      (node (ref "RASPBERRY-BOTTOM2") (pin "31") (pinfunction "31_31") (pintype "unspecified"))
      (node (ref "RASPBERRY-BOTTOM2") (pin "36") (pinfunction "36_36") (pintype "unspecified"))
      (node (ref "RASPBERRY-BOTTOM2") (pin "8") (pinfunction "8_8") (pintype "unspecified"))
      (node (ref "RASPBERRY-TOP1") (pin "14") (pinfunction "14_14") (pintype "unspecified"))
      (node (ref "RASPBERRY-TOP1") (pin "20") (pinfunction "20_20") (pintype "unspecified"))
      (node (ref "RASPBERRY-TOP1") (pin "25") (pinfunction "25_25") (pintype "unspecified"))
      (node (ref "RASPBERRY-TOP1") (pin "30") (pinfunction "30_30") (pintype "unspecified"))
      (node (ref "RASPBERRY-TOP1") (pin "34") (pinfunction "34_34") (pintype "unspecified"))
      (node (ref "RASPBERRY-TOP1") (pin "39") (pinfunction "39_39") (pintype "unspecified"))
      (node (ref "RASPBERRY-TOP1") (pin "6") (pinfunction "6_6") (pintype "unspecified"))
      (node (ref "RASPBERRY-TOP1") (pin "9") (pinfunction "9_9") (pintype "unspecified"))
      (node (ref "SW1") (pin "1") (pinfunction "1_1") (pintype "unspecified"))
      (node (ref "U10") (pin "49") (pinfunction "EP_49") (pintype "unspecified"))
      (node (ref "U2") (pin "1") (pinfunction "ADJ(GND)_1") (pintype "unspecified"))
      (node (ref "U3") (pin "1") (pinfunction "ADJ(GND)_1") (pintype "unspecified"))
      (node (ref "VLOGIC1") (pin "11") (pinfunction "GND_11") (pintype "unspecified"))
    )
    (net (code "38") (name "GPIO0") (class "Default")
      (node (ref "RASPBERRY-BOTTOM2") (pin "13") (pinfunction "13_13") (pintype "unspecified"))
      (node (ref "RASPBERRY-TOP1") (pin "27") (pinfunction "27_27") (pintype "unspecified"))
    )
    (net (code "39") (name "GPIO1") (class "Default")
      (node (ref "RASPBERRY-BOTTOM2") (pin "14") (pinfunction "14_14") (pintype "unspecified"))
      (node (ref "RASPBERRY-TOP1") (pin "28") (pinfunction "28_28") (pintype "unspecified"))
    )
    (net (code "40") (name "GPIO4") (class "Default")
      (node (ref "RASPBERRY-BOTTOM2") (pin "33") (pinfunction "33_33") (pintype "unspecified"))
      (node (ref "RASPBERRY-TOP1") (pin "7") (pinfunction "7_7") (pintype "unspecified"))
    )
    (net (code "41") (name "GPIO5") (class "Default")
      (node (ref "RASPBERRY-BOTTOM2") (pin "11") (pinfunction "11_11") (pintype "unspecified"))
      (node (ref "RASPBERRY-TOP1") (pin "29") (pinfunction "29_29") (pintype "unspecified"))
    )
    (net (code "42") (name "GPIO6") (class "Default")
      (node (ref "RASPBERRY-BOTTOM2") (pin "9") (pinfunction "9_9") (pintype "unspecified"))
      (node (ref "RASPBERRY-TOP1") (pin "31") (pinfunction "31_31") (pintype "unspecified"))
    )
    (net (code "43") (name "GPIO7") (class "Default")
      (node (ref "RASPBERRY-BOTTOM2") (pin "16") (pinfunction "16_16") (pintype "unspecified"))
      (node (ref "RASPBERRY-TOP1") (pin "26") (pinfunction "26_26") (pintype "unspecified"))
    )
    (net (code "44") (name "GPIO8") (class "Default")
      (node (ref "RASPBERRY-BOTTOM2") (pin "18") (pinfunction "18_18") (pintype "unspecified"))
      (node (ref "RASPBERRY-TOP1") (pin "24") (pinfunction "24_24") (pintype "unspecified"))
    )
    (net (code "45") (name "GPIO9") (class "Default")
      (node (ref "RASPBERRY-BOTTOM2") (pin "19") (pinfunction "19_19") (pintype "unspecified"))
      (node (ref "RASPBERRY-TOP1") (pin "21") (pinfunction "21_21") (pintype "unspecified"))
    )
    (net (code "46") (name "GPIO10") (class "Default")
      (node (ref "RASPBERRY-BOTTOM2") (pin "21") (pinfunction "21_21") (pintype "unspecified"))
      (node (ref "RASPBERRY-TOP1") (pin "19") (pinfunction "19_19") (pintype "unspecified"))
    )
    (net (code "47") (name "GPIO11") (class "Default")
      (node (ref "RASPBERRY-BOTTOM2") (pin "17") (pinfunction "17_17") (pintype "unspecified"))
      (node (ref "RASPBERRY-TOP1") (pin "23") (pinfunction "23_23") (pintype "unspecified"))
    )
    (net (code "48") (name "GPIO12") (class "Default")
      (node (ref "RASPBERRY-BOTTOM2") (pin "10") (pinfunction "10_10") (pintype "unspecified"))
      (node (ref "RASPBERRY-TOP1") (pin "32") (pinfunction "32_32") (pintype "unspecified"))
    )
    (net (code "49") (name "GPIO13") (class "Default")
      (node (ref "RASPBERRY-BOTTOM2") (pin "7") (pinfunction "7_7") (pintype "unspecified"))
      (node (ref "RASPBERRY-TOP1") (pin "33") (pinfunction "33_33") (pintype "unspecified"))
    )
    (net (code "50") (name "GPIO17") (class "Default")
      (node (ref "RASPBERRY-BOTTOM2") (pin "29") (pinfunction "29_29") (pintype "unspecified"))
      (node (ref "RASPBERRY-TOP1") (pin "11") (pinfunction "11_11") (pintype "unspecified"))
    )
    (net (code "51") (name "GPIO18") (class "Default")
      (node (ref "RASPBERRY-BOTTOM2") (pin "30") (pinfunction "30_30") (pintype "unspecified"))
      (node (ref "RASPBERRY-TOP1") (pin "12") (pinfunction "12_12") (pintype "unspecified"))
    )
    (net (code "52") (name "GPIO22") (class "Default")
      (node (ref "RASPBERRY-BOTTOM2") (pin "25") (pinfunction "25_25") (pintype "unspecified"))
      (node (ref "RASPBERRY-TOP1") (pin "15") (pinfunction "15_15") (pintype "unspecified"))
    )
    (net (code "53") (name "GPIO23") (class "Default")
      (node (ref "RASPBERRY-BOTTOM2") (pin "26") (pinfunction "26_26") (pintype "unspecified"))
      (node (ref "RASPBERRY-TOP1") (pin "16") (pinfunction "16_16") (pintype "unspecified"))
    )
    (net (code "54") (name "GPIO24") (class "Default")
      (node (ref "RASPBERRY-BOTTOM2") (pin "24") (pinfunction "24_24") (pintype "unspecified"))
      (node (ref "RASPBERRY-TOP1") (pin "18") (pinfunction "18_18") (pintype "unspecified"))
    )
    (net (code "55") (name "GPIO25") (class "Default")
      (node (ref "RASPBERRY-BOTTOM2") (pin "20") (pinfunction "20_20") (pintype "unspecified"))
      (node (ref "RASPBERRY-TOP1") (pin "22") (pinfunction "22_22") (pintype "unspecified"))
    )
    (net (code "56") (name "GPIO27") (class "Default")
      (node (ref "RASPBERRY-BOTTOM2") (pin "27") (pinfunction "27_27") (pintype "unspecified"))
      (node (ref "RASPBERRY-TOP1") (pin "13") (pinfunction "13_13") (pintype "unspecified"))
    )
    (net (code "57") (name "I2C_SCL") (class "Default")
      (node (ref "DAC1") (pin "5") (pinfunction "SCL_5") (pintype "unspecified"))
      (node (ref "DAC2") (pin "5") (pinfunction "SCL_5") (pintype "unspecified"))
      (node (ref "FPC1") (pin "19") (pinfunction "19_19") (pintype "unspecified"))
      (node (ref "R16") (pin "1") (pinfunction "1_1") (pintype "unspecified"))
      (node (ref "RASPBERRY-BOTTOM2") (pin "35") (pinfunction "35_35") (pintype "unspecified"))
      (node (ref "RASPBERRY-TOP1") (pin "5") (pinfunction "5_5") (pintype "unspecified"))
      (node (ref "U10") (pin "37") (pinfunction "IOT_45a_G1_37") (pintype "unspecified"))
    )
    (net (code "58") (name "I2C_SDA") (class "Default")
      (node (ref "DAC1") (pin "4") (pinfunction "SDA_4") (pintype "bidirectional"))
      (node (ref "DAC2") (pin "4") (pinfunction "SDA_4") (pintype "bidirectional"))
      (node (ref "FPC1") (pin "20") (pinfunction "20_20") (pintype "unspecified"))
      (node (ref "R17") (pin "1") (pinfunction "1_1") (pintype "unspecified"))
      (node (ref "RASPBERRY-BOTTOM2") (pin "37") (pinfunction "37_37") (pintype "unspecified"))
      (node (ref "RASPBERRY-TOP1") (pin "3") (pinfunction "3_3") (pintype "unspecified"))
      (node (ref "U10") (pin "38") (pinfunction "IOT_50b_38") (pintype "unspecified"))
    )
    (net (code "59") (name "Net-(CLK1-VDD)") (class "Default")
      (node (ref "CLK1") (pin "4") (pinfunction "VDD_4") (pintype "unspecified"))
      (node (ref "RN2") (pin "6") (pinfunction "6_6") (pintype "unspecified"))
      (node (ref "RN2") (pin "7") (pinfunction "7_7") (pintype "unspecified"))
      (node (ref "RN2") (pin "8") (pinfunction "8_8") (pintype "unspecified"))
    )
    (net (code "60") (name "Net-(D1-A)") (class "Default")
      (node (ref "C1") (pin "1") (pinfunction "1_1") (pintype "input"))
      (node (ref "D1") (pin "2") (pinfunction "A_2") (pintype "unspecified"))
      (node (ref "U1") (pin "1") (pinfunction "1_1") (pintype "unspecified"))
    )
    (net (code "61") (name "Net-(DAC1-A0)") (class "Default")
      (node (ref "DAC1") (pin "6") (pinfunction "A0_6") (pintype "unspecified"))
      (node (ref "R20") (pin "2") (pinfunction "2_2") (pintype "unspecified"))
    )
    (net (code "62") (name "Net-(DAC2-A0)") (class "Default")
      (node (ref "DAC2") (pin "6") (pinfunction "A0_6") (pintype "unspecified"))
      (node (ref "R21") (pin "2") (pinfunction "2_2") (pintype "unspecified"))
    )
    (net (code "63") (name "Net-(FLASH1-CS#)") (class "Default")
      (node (ref "FLASH1") (pin "1") (pinfunction "CS#_1") (pintype "unspecified"))
      (node (ref "R10") (pin "1") (pinfunction "1_1") (pintype "unspecified"))
      (node (ref "R9") (pin "2") (pinfunction "2_2") (pintype "unspecified"))
    )
    (net (code "64") (name "Net-(FLASH1-HOLD#orRESET#(IO3))") (class "Default")
      (node (ref "FLASH1") (pin "7") (pinfunction "HOLD#orRESET#(IO3)_7") (pintype "unspecified"))
      (node (ref "R7") (pin "1") (pinfunction "1_1") (pintype "unspecified"))
    )
    (net (code "65") (name "Net-(FLASH1-WP#(IO2))") (class "Default")
      (node (ref "FLASH1") (pin "3") (pinfunction "WP#(IO2)_3") (pintype "unspecified"))
      (node (ref "R11") (pin "1") (pinfunction "1_1") (pintype "unspecified"))
    )
    (net (code "66") (name "Net-(FPC1-Pad25)") (class "Default")
      (node (ref "FPC1") (pin "25") (pinfunction "25_25") (pintype "unspecified"))
      (node (ref "RN4") (pin "1") (pinfunction "1_1") (pintype "unspecified"))
    )
    (net (code "67") (name "Net-(FPC1-Pad26)") (class "Default")
      (node (ref "FPC1") (pin "26") (pinfunction "26_26") (pintype "unspecified"))
      (node (ref "RN4") (pin "2") (pinfunction "2_2") (pintype "unspecified"))
    )
    (net (code "68") (name "Net-(FPC1-Pad27)") (class "Default")
      (node (ref "FPC1") (pin "27") (pinfunction "27_27") (pintype "unspecified"))
      (node (ref "RN4") (pin "3") (pinfunction "3_3") (pintype "unspecified"))
    )
    (net (code "69") (name "Net-(FPC1-Pad28)") (class "Default")
      (node (ref "FPC1") (pin "28") (pinfunction "28_28") (pintype "unspecified"))
      (node (ref "RN4") (pin "4") (pinfunction "4_4") (pintype "unspecified"))
    )
    (net (code "70") (name "Net-(FPC1-Pad29)") (class "Default")
      (node (ref "FPC1") (pin "29") (pinfunction "29_29") (pintype "unspecified"))
      (node (ref "RN5") (pin "1") (pinfunction "1_1") (pintype "unspecified"))
    )
    (net (code "71") (name "Net-(FPC1-Pad30)") (class "Default")
      (node (ref "FPC1") (pin "30") (pinfunction "30_30") (pintype "unspecified"))
      (node (ref "RN5") (pin "2") (pinfunction "2_2") (pintype "unspecified"))
    )
    (net (code "72") (name "Net-(FPC1-Pad31)") (class "Default")
      (node (ref "FPC1") (pin "31") (pinfunction "31_31") (pintype "unspecified"))
      (node (ref "RN5") (pin "3") (pinfunction "3_3") (pintype "unspecified"))
    )
    (net (code "73") (name "Net-(FPC1-Pad32)") (class "Default")
      (node (ref "FPC1") (pin "32") (pinfunction "32_32") (pintype "unspecified"))
      (node (ref "RN5") (pin "4") (pinfunction "4_4") (pintype "unspecified"))
    )
    (net (code "74") (name "Net-(FPC1-Pad33)") (class "Default")
      (node (ref "FPC1") (pin "33") (pinfunction "33_33") (pintype "unspecified"))
      (node (ref "RN6") (pin "1") (pinfunction "1_1") (pintype "unspecified"))
    )
    (net (code "75") (name "Net-(FPC1-Pad34)") (class "Default")
      (node (ref "FPC1") (pin "34") (pinfunction "34_34") (pintype "unspecified"))
      (node (ref "RN6") (pin "2") (pinfunction "2_2") (pintype "unspecified"))
    )
    (net (code "76") (name "Net-(FPC1-Pad35)") (class "Default")
      (node (ref "FPC1") (pin "35") (pinfunction "35_35") (pintype "unspecified"))
      (node (ref "RN6") (pin "3") (pinfunction "3_3") (pintype "unspecified"))
    )
    (net (code "77") (name "Net-(FPC1-Pad36)") (class "Default")
      (node (ref "FPC1") (pin "36") (pinfunction "36_36") (pintype "unspecified"))
      (node (ref "RN6") (pin "4") (pinfunction "4_4") (pintype "unspecified"))
    )
    (net (code "78") (name "Net-(FPC1-Pad42)") (class "Default")
      (node (ref "FPC1") (pin "42") (pinfunction "42_42") (pintype "unspecified"))
      (node (ref "RN1") (pin "1") (pinfunction "1_1") (pintype "unspecified"))
    )
    (net (code "79") (name "Net-(FPC1-Pad43)") (class "Default")
      (node (ref "FPC1") (pin "43") (pinfunction "43_43") (pintype "unspecified"))
      (node (ref "RN1") (pin "2") (pinfunction "2_2") (pintype "unspecified"))
    )
    (net (code "80") (name "Net-(FPC1-Pad44)") (class "Default")
      (node (ref "FPC1") (pin "44") (pinfunction "44_44") (pintype "unspecified"))
      (node (ref "RN1") (pin "3") (pinfunction "3_3") (pintype "unspecified"))
    )
    (net (code "81") (name "Net-(FPC1-Pad45)") (class "Default")
      (node (ref "FPC1") (pin "45") (pinfunction "45_45") (pintype "unspecified"))
      (node (ref "RN1") (pin "4") (pinfunction "4_4") (pintype "unspecified"))
    )
    (net (code "82") (name "Net-(FPC1-Pad46)") (class "Default")
      (node (ref "FPC1") (pin "46") (pinfunction "46_46") (pintype "unspecified"))
      (node (ref "RN3") (pin "1") (pinfunction "1_1") (pintype "unspecified"))
    )
    (net (code "83") (name "Net-(FPC1-Pad47)") (class "Default")
      (node (ref "FPC1") (pin "47") (pinfunction "47_47") (pintype "unspecified"))
      (node (ref "RN3") (pin "2") (pinfunction "2_2") (pintype "unspecified"))
    )
    (net (code "84") (name "Net-(FPC1-Pad48)") (class "Default")
      (node (ref "FPC1") (pin "48") (pinfunction "48_48") (pintype "unspecified"))
      (node (ref "RN3") (pin "3") (pinfunction "3_3") (pintype "unspecified"))
    )
    (net (code "85") (name "Net-(FPC1-Pad49)") (class "Default")
      (node (ref "FPC1") (pin "49") (pinfunction "49_49") (pintype "unspecified"))
      (node (ref "RN3") (pin "4") (pinfunction "4_4") (pintype "unspecified"))
    )
    (net (code "86") (name "Net-(LED2-Pad1)") (class "Default")
      (node (ref "LED2") (pin "1") (pinfunction "1_1") (pintype "unspecified"))
      (node (ref "R5") (pin "1") (pinfunction "1_1") (pintype "input"))
    )
    (net (code "87") (name "Net-(RN2-Pad1)") (class "Default")
      (node (ref "RN2") (pin "1") (pinfunction "1_1") (pintype "unspecified"))
      (node (ref "RN2") (pin "2") (pinfunction "2_2") (pintype "unspecified"))
      (node (ref "RN2") (pin "3") (pinfunction "3_3") (pintype "unspecified"))
      (node (ref "RN2") (pin "4") (pinfunction "4_4") (pintype "unspecified"))
    )
    (net (code "88") (name "PWM-RGB0") (class "Default")
      (node (ref "FPC1") (pin "38") (pinfunction "38_38") (pintype "unspecified"))
      (node (ref "U10") (pin "39") (pinfunction "RGB0_39") (pintype "unspecified"))
    )
    (net (code "89") (name "PWM-RGB1") (class "Default")
      (node (ref "FPC1") (pin "39") (pinfunction "39_39") (pintype "unspecified"))
      (node (ref "U10") (pin "40") (pinfunction "RGB1_40") (pintype "unspecified"))
    )
    (net (code "90") (name "PWM-RGB2") (class "Default")
      (node (ref "FPC1") (pin "40") (pinfunction "40_40") (pintype "unspecified"))
      (node (ref "U10") (pin "41") (pinfunction "RGB2_41") (pintype "unspecified"))
    )
    (net (code "91") (name "PWR1v2") (class "Default")
      (node (ref "C8") (pin "1") (pinfunction "1_1") (pintype "input"))
      (node (ref "C9") (pin "2") (pinfunction "2_2") (pintype "input"))
      (node (ref "R1") (pin "1") (pinfunction "1_1") (pintype "unspecified"))
      (node (ref "R2") (pin "1") (pinfunction "1_1") (pintype "unspecified"))
      (node (ref "U3") (pin "4") (pinfunction "TAB_4") (pintype "unspecified"))
    )
    (net (code "92") (name "PWR3v3") (class "Default")
      (node (ref "C6") (pin "1") (pinfunction "1_1") (pintype "input"))
      (node (ref "C7") (pin "2") (pinfunction "2_2") (pintype "input"))
      (node (ref "D2") (pin "2") (pinfunction "A_2") (pintype "unspecified"))
      (node (ref "R3") (pin "1") (pinfunction "1_1") (pintype "unspecified"))
      (node (ref "U2") (pin "4") (pinfunction "TAB_4") (pintype "unspecified"))
    )
    (net (code "93") (name "PWR5v") (class "Default")
      (node (ref "C2") (pin "1") (pinfunction "1_1") (pintype "input"))
      (node (ref "C3") (pin "2") (pinfunction "2_2") (pintype "input"))
      (node (ref "C4") (pin "2") (pinfunction "2_2") (pintype "input"))
      (node (ref "C5") (pin "2") (pinfunction "2_2") (pintype "input"))
      (node (ref "D1") (pin "1") (pinfunction "C_1") (pintype "unspecified"))
      (node (ref "R5") (pin "2") (pinfunction "2_2") (pintype "input"))
      (node (ref "U2") (pin "3") (pinfunction "VIN_3") (pintype "unspecified"))
      (node (ref "U3") (pin "3") (pinfunction "VIN_3") (pintype "unspecified"))
      (node (ref "VLOGIC1") (pin "19") (pinfunction "VCCB_19") (pintype "unspecified"))
    )
    (net (code "94") (name "SCLK-ICE") (class "Default")
      (node (ref "FLASH1") (pin "6") (pinfunction "CLK_6") (pintype "unspecified"))
      (node (ref "R8") (pin "1") (pinfunction "1_1") (pintype "unspecified"))
      (node (ref "RASPBERRY-BOTTOM2") (pin "6") (pinfunction "6_6") (pintype "unspecified"))
      (node (ref "RASPBERRY-TOP1") (pin "36") (pinfunction "36_36") (pintype "unspecified"))
      (node (ref "U10") (pin "15") (pinfunction "IOB_34a_SPI_SCK_15") (pintype "unspecified"))
    )
    (net (code "95") (name "SDI") (class "Default")
      (node (ref "FLASH1") (pin "5") (pinfunction "DI(IO0)_5") (pintype "unspecified"))
      (node (ref "R13") (pin "1") (pinfunction "1_1") (pintype "unspecified"))
      (node (ref "RASPBERRY-BOTTOM2") (pin "4") (pinfunction "4_4") (pintype "unspecified"))
      (node (ref "RASPBERRY-TOP1") (pin "38") (pinfunction "38_38") (pintype "unspecified"))
    )
    (net (code "96") (name "SDI-ICE") (class "Default")
      (node (ref "R12") (pin "2") (pinfunction "2_2") (pintype "unspecified"))
      (node (ref "U10") (pin "17") (pinfunction "IOB_33b_SPI_SI_17") (pintype "unspecified"))
    )
    (net (code "97") (name "SDO") (class "Default")
      (node (ref "FLASH1") (pin "2") (pinfunction "DO(IO1)_2") (pintype "unspecified"))
      (node (ref "R12") (pin "1") (pinfunction "1_1") (pintype "unspecified"))
      (node (ref "RASPBERRY-BOTTOM2") (pin "5") (pinfunction "5_5") (pintype "unspecified"))
      (node (ref "RASPBERRY-TOP1") (pin "35") (pinfunction "35_35") (pintype "unspecified"))
    )
    (net (code "98") (name "SDO-ICE") (class "Default")
      (node (ref "R13") (pin "2") (pinfunction "2_2") (pintype "unspecified"))
      (node (ref "U10") (pin "14") (pinfunction "IOB_32a_SPI_SO_14") (pintype "unspecified"))
    )
    (net (code "99") (name "SHDN") (class "Default")
      (node (ref "ADC1") (pin "10") (pinfunction "SHDN#_10") (pintype "unspecified"))
      (node (ref "R14") (pin "2") (pinfunction "2_2") (pintype "unspecified"))
      (node (ref "U10") (pin "43") (pinfunction "IOT_49a_43") (pintype "unspecified"))
    )
    (net (code "100") (name "UART-RXD") (class "Default")
      (node (ref "FPC1") (pin "22") (pinfunction "22_22") (pintype "unspecified"))
      (node (ref "R18") (pin "1") (pinfunction "1_1") (pintype "unspecified"))
      (node (ref "RASPBERRY-BOTTOM2") (pin "34") (pinfunction "34_34") (pintype "unspecified"))
      (node (ref "RASPBERRY-TOP1") (pin "8") (pinfunction "8_8") (pintype "unspecified"))
      (node (ref "U10") (pin "4") (pinfunction "IOB_8a_4") (pintype "unspecified"))
    )
    (net (code "101") (name "UART-TXD") (class "Default")
      (node (ref "FPC1") (pin "23") (pinfunction "23_23") (pintype "unspecified"))
      (node (ref "R19") (pin "1") (pinfunction "1_1") (pintype "unspecified"))
      (node (ref "RASPBERRY-BOTTOM2") (pin "32") (pinfunction "32_32") (pintype "unspecified"))
      (node (ref "RASPBERRY-TOP1") (pin "10") (pinfunction "10_10") (pintype "unspecified"))
      (node (ref "U10") (pin "6") (pinfunction "IOB_13b_6") (pintype "unspecified"))
    )
    (net (code "102") (name "Vcc") (class "Default")
      (node (ref "C16") (pin "2") (pinfunction "2_2") (pintype "input"))
      (node (ref "C17") (pin "2") (pinfunction "2_2") (pintype "input"))
      (node (ref "C18") (pin "2") (pinfunction "2_2") (pintype "input"))
      (node (ref "C19") (pin "2") (pinfunction "2_2") (pintype "input"))
      (node (ref "C20") (pin "2") (pinfunction "2_2") (pintype "input"))
      (node (ref "C21") (pin "1") (pinfunction "1_1") (pintype "input"))
      (node (ref "R2") (pin "2") (pinfunction "2_2") (pintype "unspecified"))
      (node (ref "U10") (pin "30") (pinfunction "VCC_30") (pintype "unspecified"))
      (node (ref "U10") (pin "5") (pinfunction "VCC_5") (pintype "unspecified"))
    )
    (net (code "103") (name "Vcc-5v") (class "Default")
      (node (ref "RASPBERRY-BOTTOM2") (pin "38") (pinfunction "38_38") (pintype "unspecified"))
      (node (ref "RASPBERRY-TOP1") (pin "4") (pinfunction "4_4") (pintype "unspecified"))
      (node (ref "U1") (pin "2") (pinfunction "2_2") (pintype "unspecified"))
    )
    (net (code "104") (name "Vccpll") (class "Default")
      (node (ref "C10") (pin "1") (pinfunction "1_1") (pintype "input"))
      (node (ref "C11") (pin "2") (pinfunction "2_2") (pintype "input"))
      (node (ref "C12") (pin "2") (pinfunction "2_2") (pintype "input"))
      (node (ref "C13") (pin "2") (pinfunction "2_2") (pintype "input"))
      (node (ref "C14") (pin "2") (pinfunction "2_2") (pintype "input"))
      (node (ref "C15") (pin "2") (pinfunction "2_2") (pintype "input"))
      (node (ref "R1") (pin "2") (pinfunction "2_2") (pintype "unspecified"))
      (node (ref "U10") (pin "29") (pinfunction "VCCPLL_29") (pintype "unspecified"))
    )
    (net (code "105") (name "Vlogic-00") (class "Default")
      (node (ref "RN3") (pin "5") (pinfunction "5_5") (pintype "unspecified"))
      (node (ref "VLOGIC1") (pin "20") (pinfunction "B1_20") (pintype "unspecified"))
    )
    (net (code "106") (name "Vlogic-00in{slash}out") (class "Default")
      (node (ref "U10") (pin "36") (pinfunction "IOT_48b_36") (pintype "unspecified"))
      (node (ref "VLOGIC1") (pin "1") (pinfunction "A1_1") (pintype "unspecified"))
    )
    (net (code "107") (name "Vlogic-01") (class "Default")
      (node (ref "RN3") (pin "6") (pinfunction "6_6") (pintype "unspecified"))
      (node (ref "VLOGIC1") (pin "18") (pinfunction "B2_18") (pintype "unspecified"))
    )
    (net (code "108") (name "Vlogic-01in{slash}out") (class "Default")
      (node (ref "U10") (pin "34") (pinfunction "IOT_44b_34") (pintype "unspecified"))
      (node (ref "VLOGIC1") (pin "3") (pinfunction "A2_3") (pintype "unspecified"))
    )
    (net (code "109") (name "Vlogic-02") (class "Default")
      (node (ref "RN3") (pin "7") (pinfunction "7_7") (pintype "unspecified"))
      (node (ref "VLOGIC1") (pin "17") (pinfunction "B3_17") (pintype "unspecified"))
    )
    (net (code "110") (name "Vlogic-02in{slash}out") (class "Default")
      (node (ref "U10") (pin "32") (pinfunction "IOT_43a_32") (pintype "unspecified"))
      (node (ref "VLOGIC1") (pin "4") (pinfunction "A3_4") (pintype "unspecified"))
    )
    (net (code "111") (name "Vlogic-03") (class "Default")
      (node (ref "RN3") (pin "8") (pinfunction "8_8") (pintype "unspecified"))
      (node (ref "VLOGIC1") (pin "16") (pinfunction "B4_16") (pintype "unspecified"))
    )
    (net (code "112") (name "Vlogic-03in{slash}out") (class "Default")
      (node (ref "U10") (pin "31") (pinfunction "IOT_42b_31") (pintype "unspecified"))
      (node (ref "VLOGIC1") (pin "5") (pinfunction "A4_5") (pintype "unspecified"))
    )
    (net (code "113") (name "Vlogic-04") (class "Default")
      (node (ref "RN1") (pin "5") (pinfunction "5_5") (pintype "unspecified"))
      (node (ref "VLOGIC1") (pin "15") (pinfunction "B5_15") (pintype "unspecified"))
    )
    (net (code "114") (name "Vlogic-04in{slash}out") (class "Default")
      (node (ref "U10") (pin "28") (pinfunction "IOT_41a_28") (pintype "unspecified"))
      (node (ref "VLOGIC1") (pin "6") (pinfunction "A5_6") (pintype "unspecified"))
    )
    (net (code "115") (name "Vlogic-05") (class "Default")
      (node (ref "RN1") (pin "6") (pinfunction "6_6") (pintype "unspecified"))
      (node (ref "VLOGIC1") (pin "14") (pinfunction "B6_14") (pintype "unspecified"))
    )
    (net (code "116") (name "Vlogic-05in{slash}out") (class "Default")
      (node (ref "U10") (pin "27") (pinfunction "IOT_38b_27") (pintype "unspecified"))
      (node (ref "VLOGIC1") (pin "7") (pinfunction "A6_7") (pintype "unspecified"))
    )
    (net (code "117") (name "Vlogic-06") (class "Default")
      (node (ref "RN1") (pin "7") (pinfunction "7_7") (pintype "unspecified"))
      (node (ref "VLOGIC1") (pin "13") (pinfunction "B7_13") (pintype "unspecified"))
    )
    (net (code "118") (name "Vlogic-06in{slash}out") (class "Default")
      (node (ref "U10") (pin "26") (pinfunction "IOT_39a_26") (pintype "unspecified"))
      (node (ref "VLOGIC1") (pin "8") (pinfunction "A7_8") (pintype "unspecified"))
    )
    (net (code "119") (name "Vlogic-07") (class "Default")
      (node (ref "RN1") (pin "8") (pinfunction "8_8") (pintype "unspecified"))
      (node (ref "VLOGIC1") (pin "12") (pinfunction "B8_12") (pintype "unspecified"))
    )
    (net (code "120") (name "Vlogic-07in{slash}out") (class "Default")
      (node (ref "U10") (pin "25") (pinfunction "IOT_36b_25") (pintype "unspecified"))
      (node (ref "VLOGIC1") (pin "9") (pinfunction "A8_9") (pintype "unspecified"))
    )
    (net (code "121") (name "Vlogic_OE") (class "Default")
      (node (ref "R15") (pin "1") (pinfunction "1_1") (pintype "unspecified"))
      (node (ref "U10") (pin "42") (pinfunction "IOT_51a_42") (pintype "unspecified"))
      (node (ref "VLOGIC1") (pin "10") (pinfunction "OE_10") (pintype "unspecified"))
    )
    (net (code "122") (name "Vpp_2v5") (class "Default")
      (node (ref "C22") (pin "1") (pinfunction "1_1") (pintype "input"))
      (node (ref "C23") (pin "2") (pinfunction "2_2") (pintype "input"))
      (node (ref "C24") (pin "2") (pinfunction "2_2") (pintype "input"))
      (node (ref "C25") (pin "2") (pinfunction "2_2") (pintype "input"))
      (node (ref "C26") (pin "2") (pinfunction "2_2") (pintype "input"))
      (node (ref "C27") (pin "2") (pinfunction "2_2") (pintype "input"))
      (node (ref "D2") (pin "1") (pinfunction "C_1") (pintype "unspecified"))
      (node (ref "U10") (pin "24") (pinfunction "VPP_2V5_24") (pintype "unspecified"))
    )
    (net (code "123") (name "unconnected-(U2-VOUT(TAB)-Pad2)") (class "Default")
      (node (ref "U2") (pin "2") (pinfunction "VOUT(TAB)_2") (pintype "unspecified+no_connect"))
    )
    (net (code "124") (name "unconnected-(U3-VOUT(TAB)-Pad2)") (class "Default")
      (node (ref "U3") (pin "2") (pinfunction "VOUT(TAB)_2") (pintype "unspecified+no_connect"))
    )
  )
)
